# AnalogConversion_v2.net
KiCad netlist of a schematic drawn in EAGLE
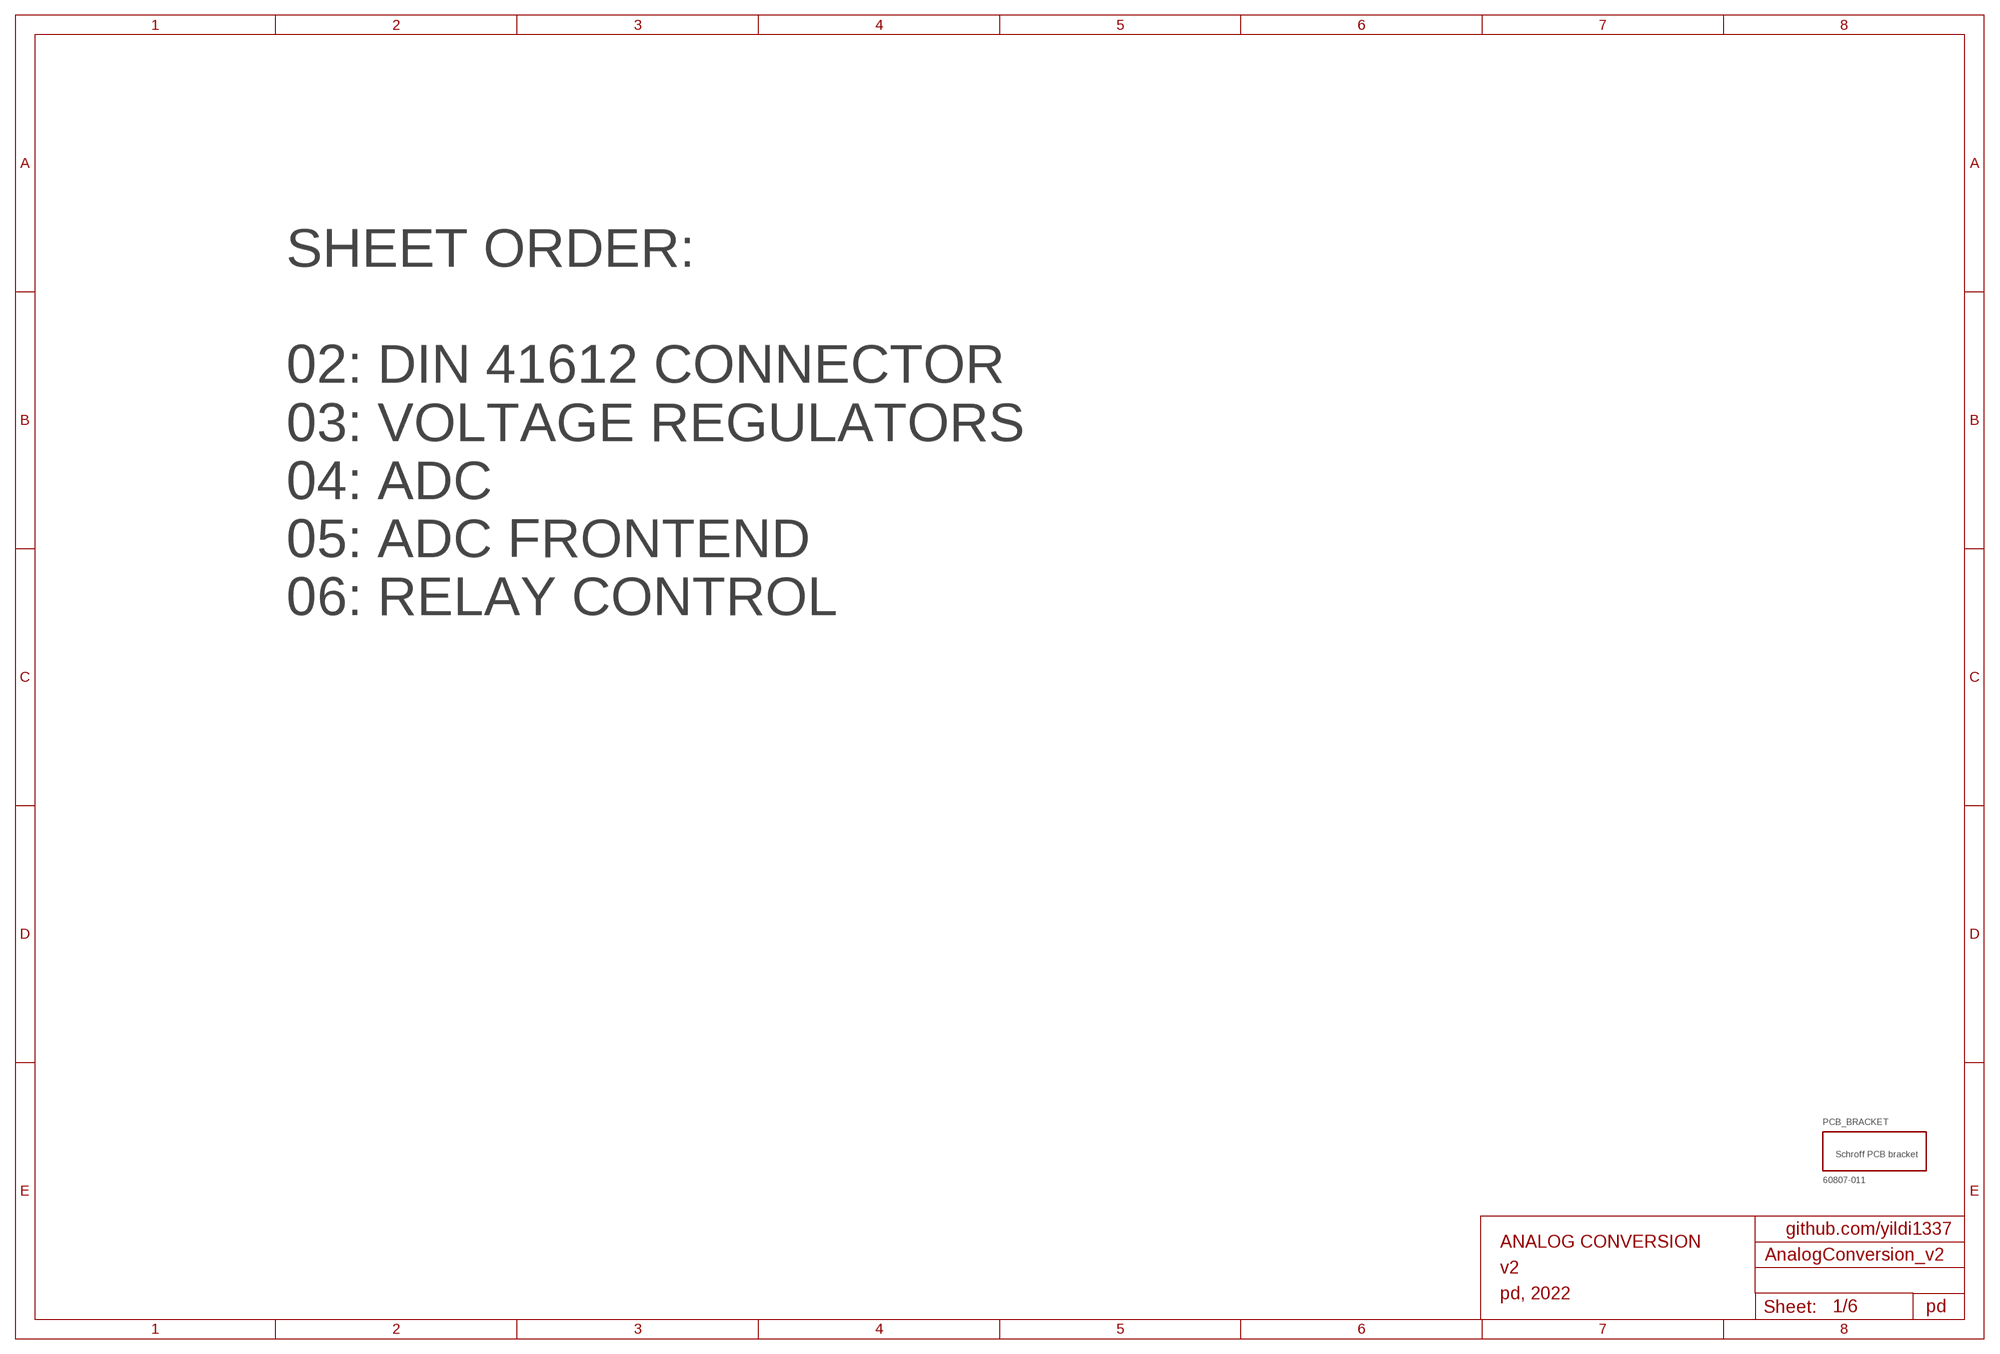
[diagram p0: schematic, sheet 1]
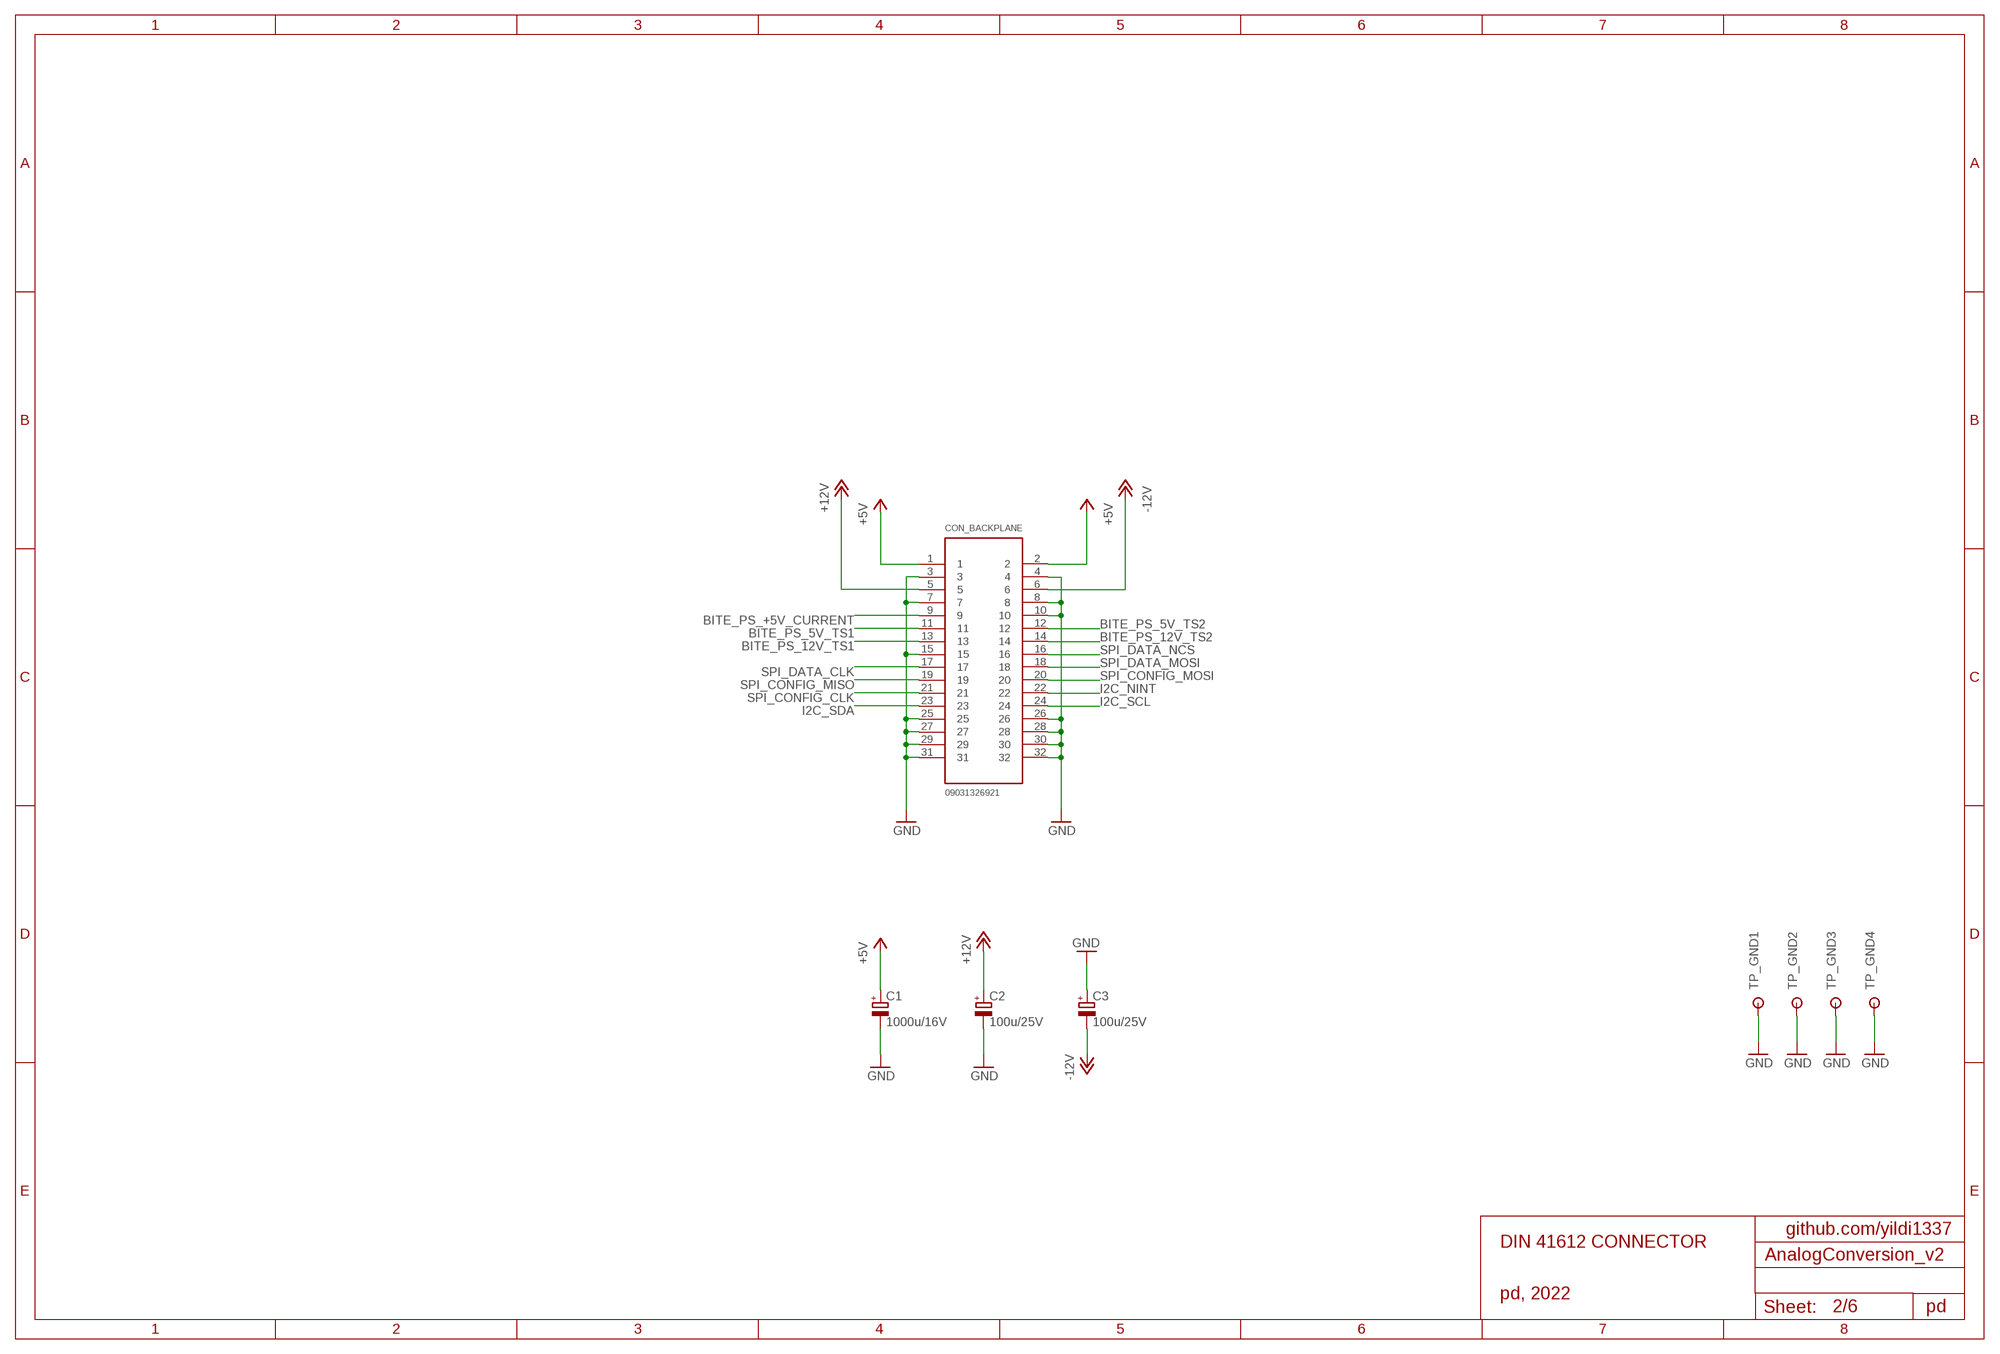
[diagram p1: schematic, sheet 2]
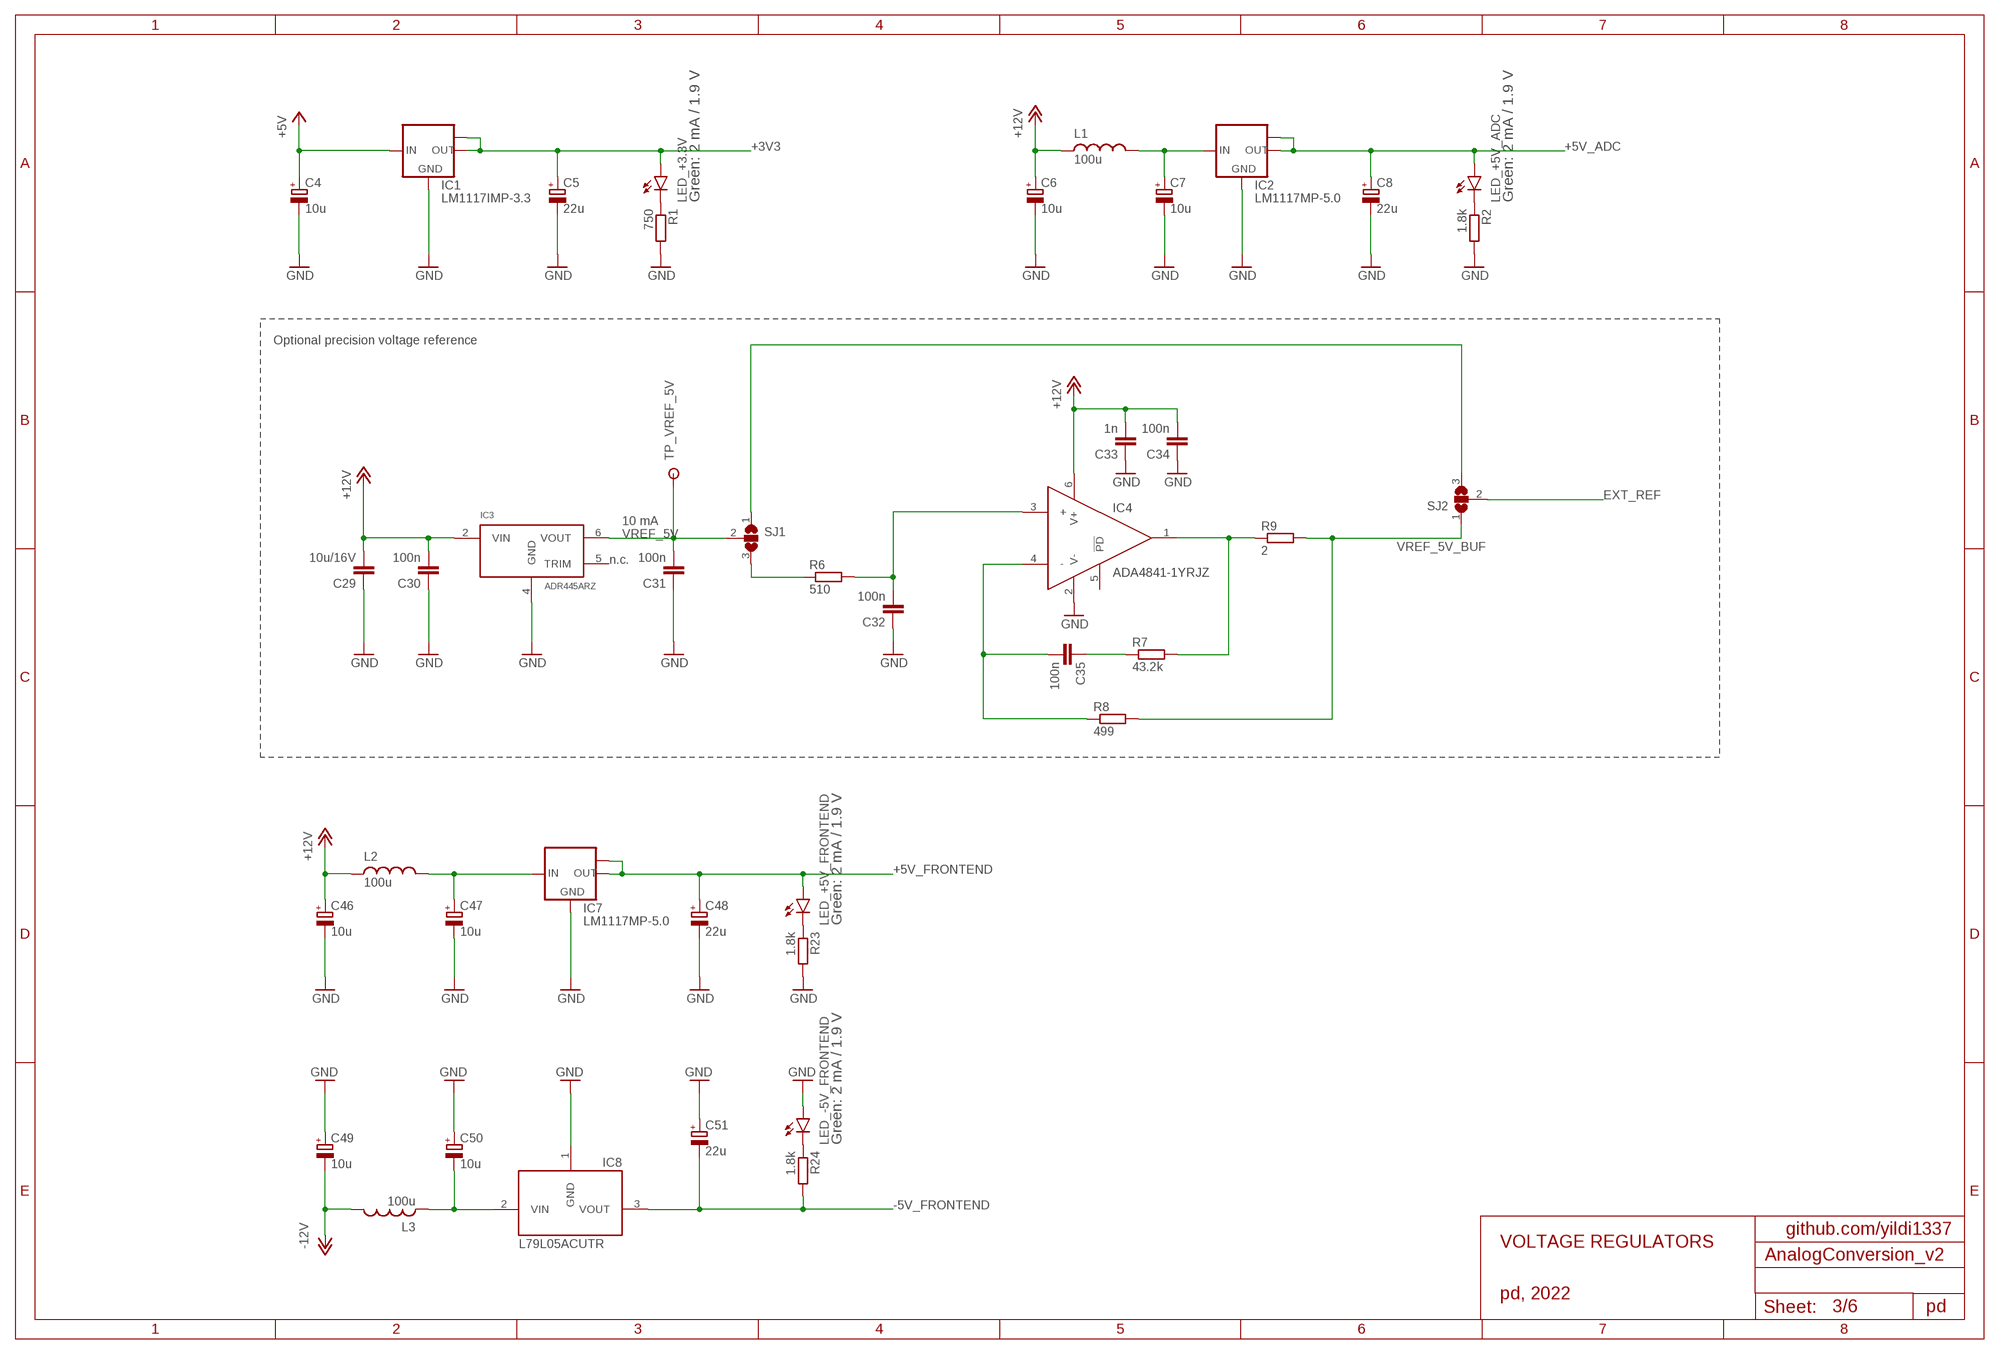
[diagram p2: schematic, sheet 3]
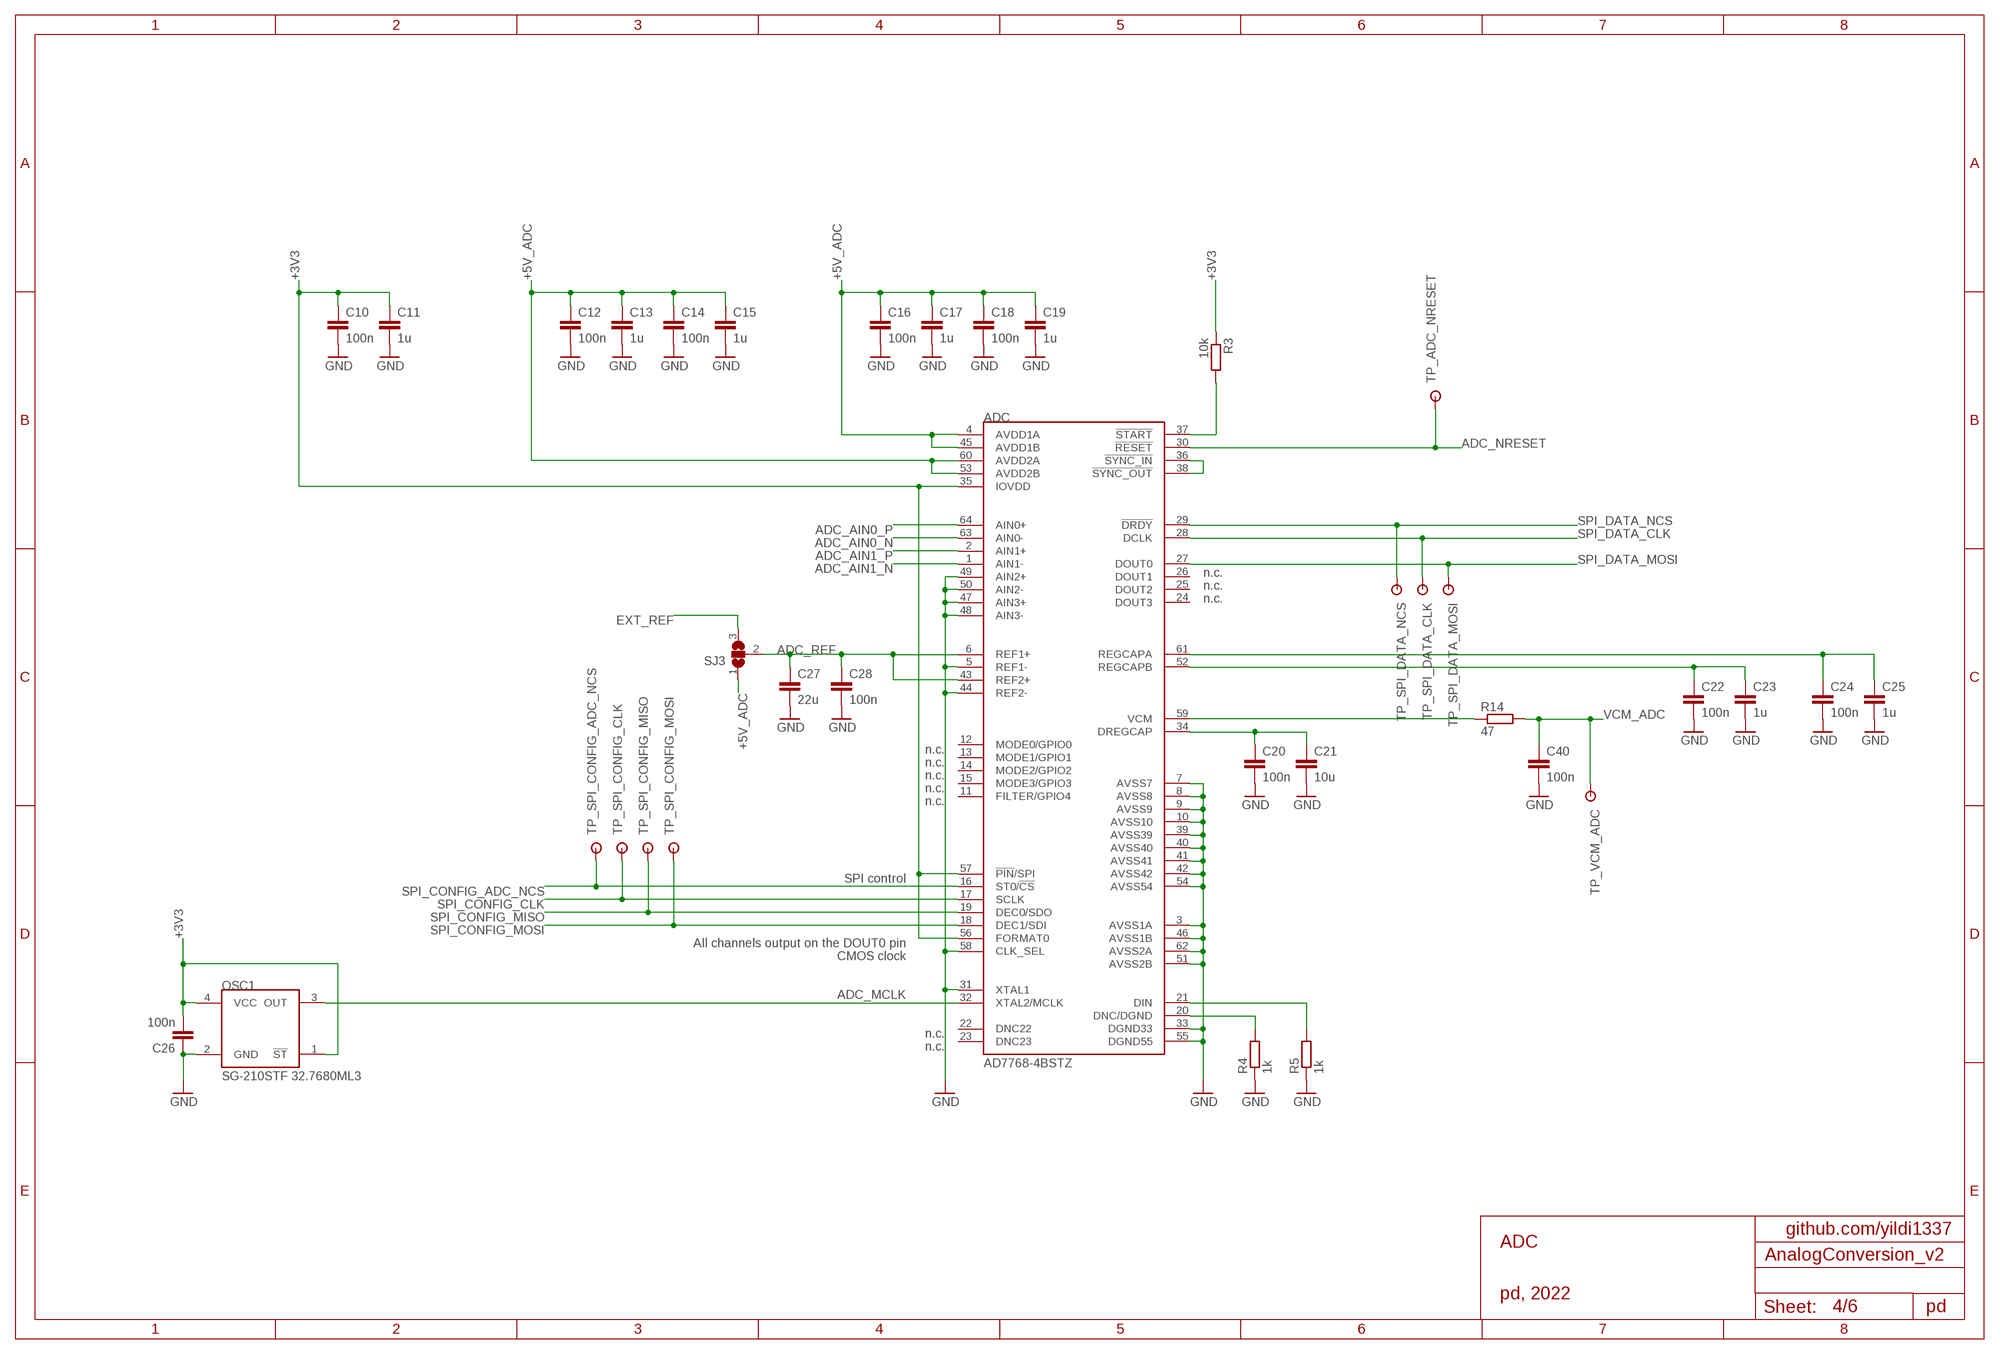
[diagram p3: schematic, sheet 4]
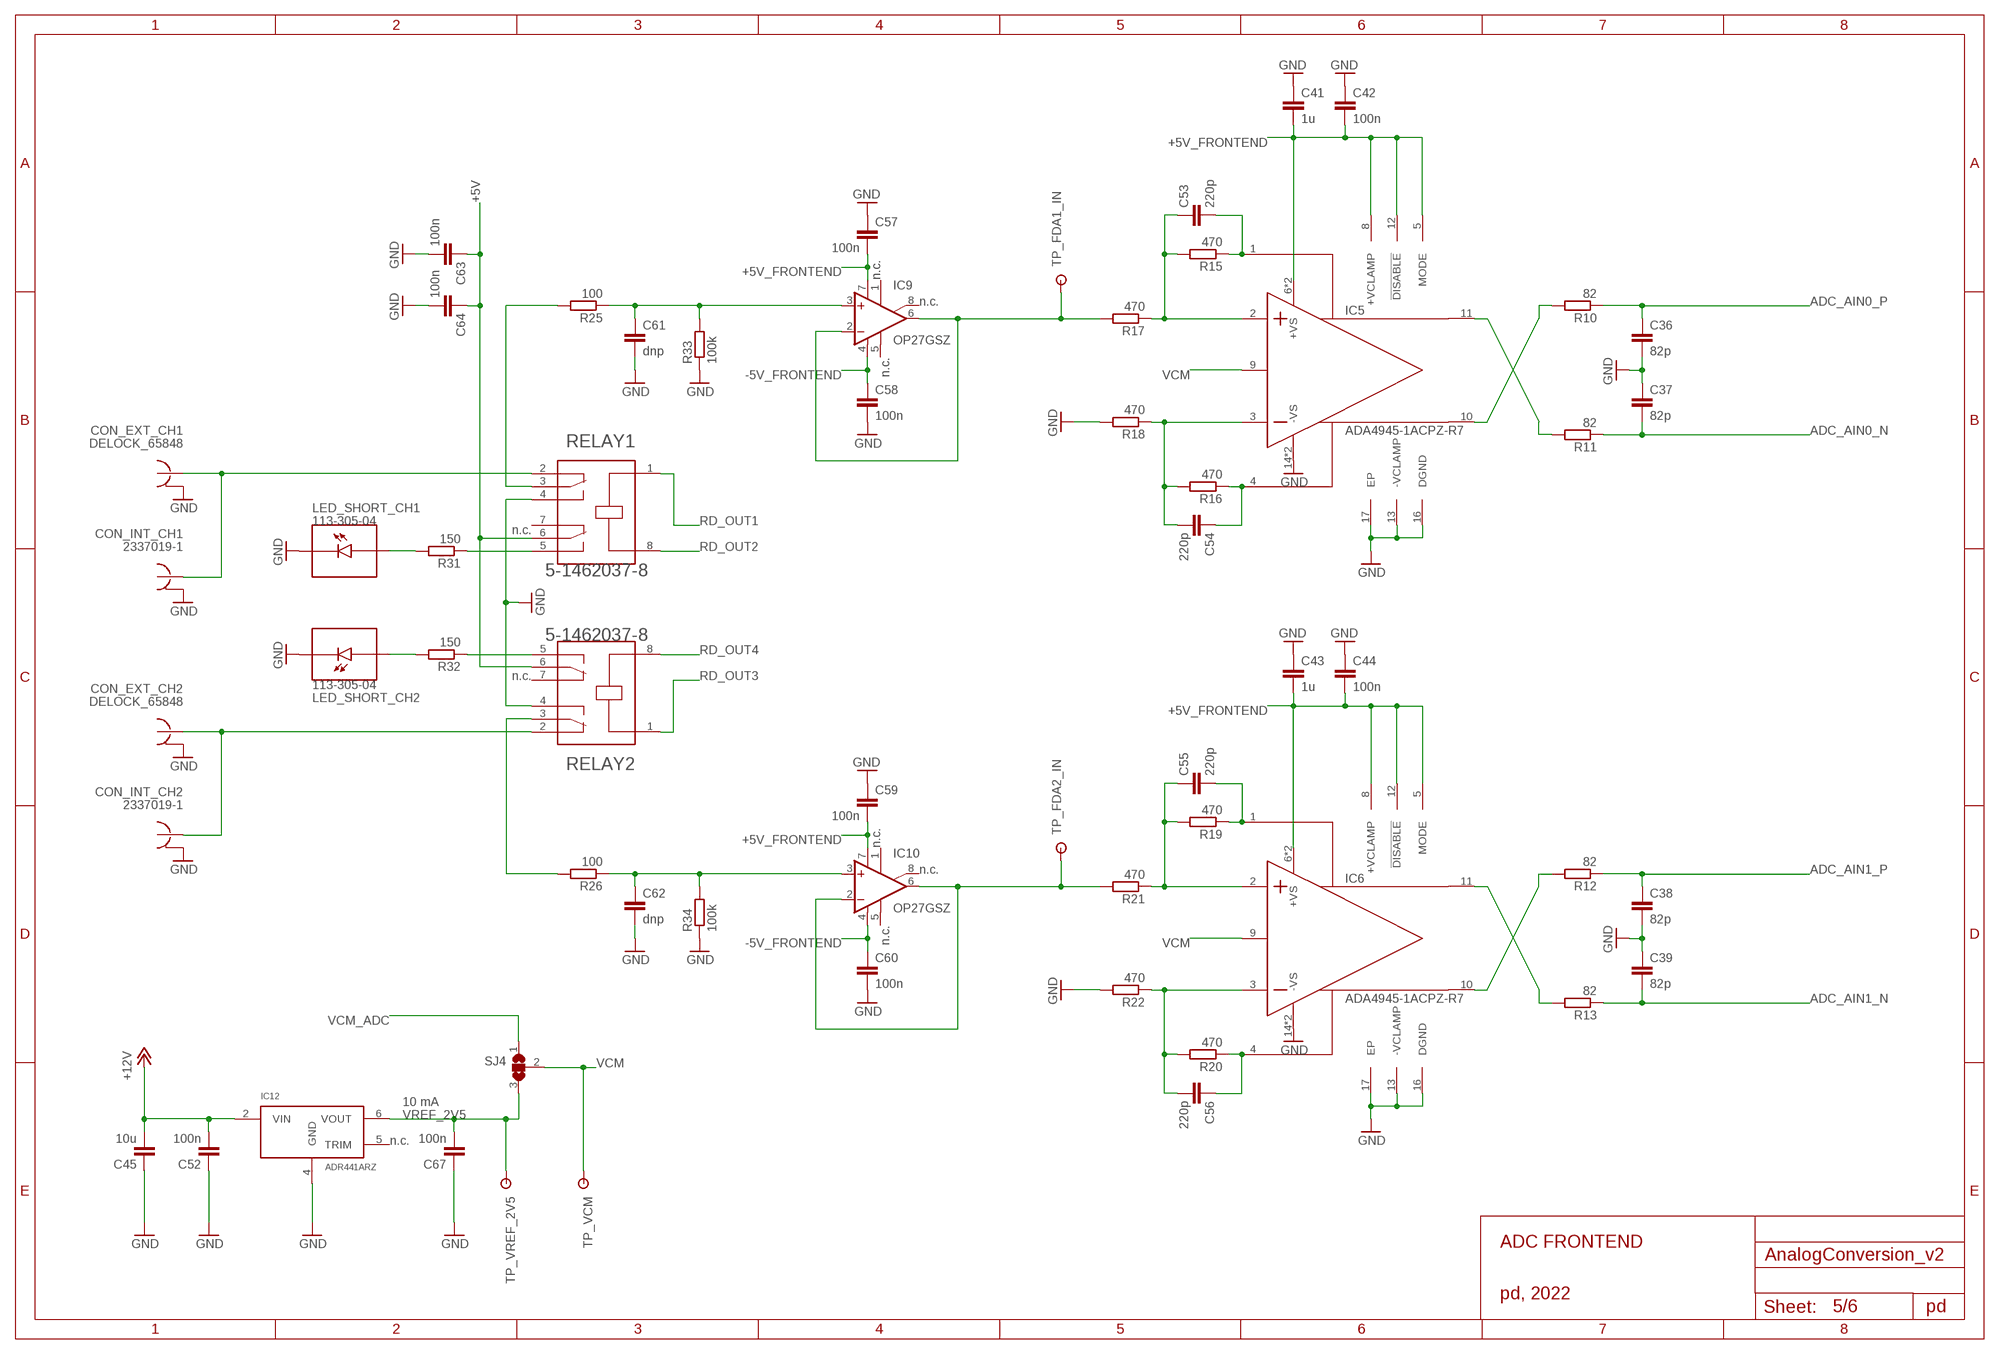
[diagram p4: schematic, sheet 5]
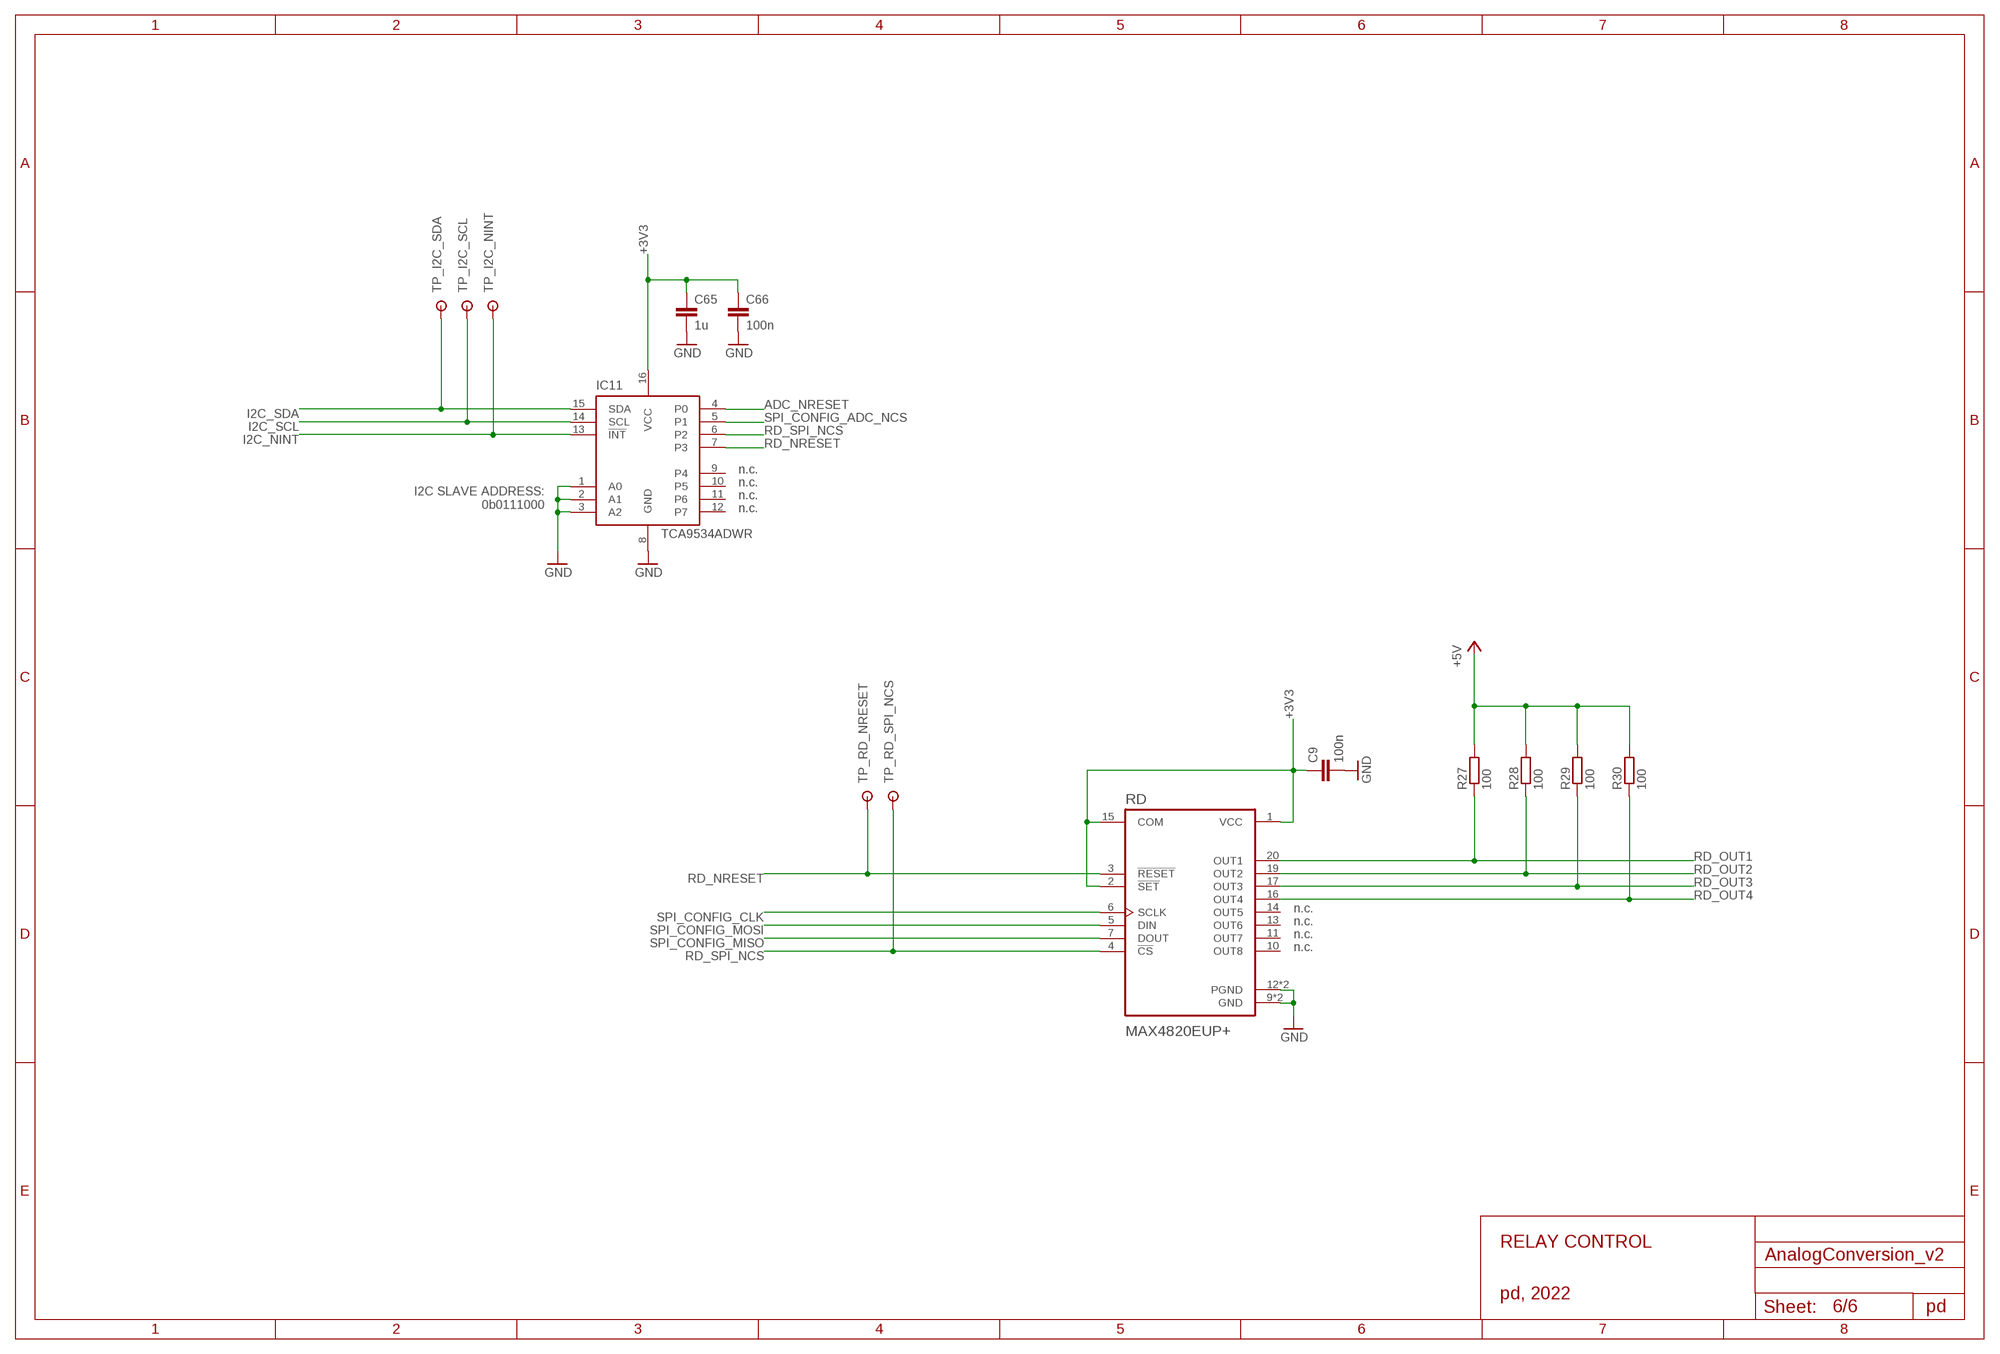
[diagram p5: schematic, sheet 6]

(export (version "E")
  (design (tool "Eeschema 10.0.6"))
  (components
    (comp (ref "ADC")
      (value "AD7768-4BSTZ")
      (footprint "eagle-import:AD7768-4BSTZ")
      (libsource (lib "eagle-import") (part "AD7768-4BSTZ"))
    )
    (comp (ref "C10")
      (value "100n")
      (footprint "eagle-import:C0603")
      (libsource (lib "eagle-import") (part "C-EUC0603"))
    )
    (comp (ref "C11")
      (value "1u")
      (footprint "eagle-import:C0603")
      (libsource (lib "eagle-import") (part "C-EUC0603"))
    )
    (comp (ref "C12")
      (value "100n")
      (footprint "eagle-import:C0603")
      (libsource (lib "eagle-import") (part "C-EUC0603"))
    )
    (comp (ref "C13")
      (value "1u")
      (footprint "eagle-import:C0603")
      (libsource (lib "eagle-import") (part "C-EUC0603"))
    )
    (comp (ref "C14")
      (value "100n")
      (footprint "eagle-import:C0603")
      (libsource (lib "eagle-import") (part "C-EUC0603"))
    )
    (comp (ref "C15")
      (value "1u")
      (footprint "eagle-import:C0603")
      (libsource (lib "eagle-import") (part "C-EUC0603"))
    )
    (comp (ref "C16")
      (value "100n")
      (footprint "eagle-import:C0603")
      (libsource (lib "eagle-import") (part "C-EUC0603"))
    )
    (comp (ref "C17")
      (value "1u")
      (footprint "eagle-import:C0603")
      (libsource (lib "eagle-import") (part "C-EUC0603"))
    )
    (comp (ref "C18")
      (value "100n")
      (footprint "eagle-import:C0603")
      (libsource (lib "eagle-import") (part "C-EUC0603"))
    )
    (comp (ref "C19")
      (value "1u")
      (footprint "eagle-import:C0603")
      (libsource (lib "eagle-import") (part "C-EUC0603"))
    )
    (comp (ref "C20")
      (value "100n")
      (footprint "eagle-import:C0603")
      (libsource (lib "eagle-import") (part "C-EUC0603"))
    )
    (comp (ref "C21")
      (value "10u")
      (footprint "eagle-import:C0603")
      (libsource (lib "eagle-import") (part "C-EUC0603"))
    )
    (comp (ref "C22")
      (value "100n")
      (footprint "eagle-import:C0603")
      (libsource (lib "eagle-import") (part "C-EUC0603"))
    )
    (comp (ref "C23")
      (value "1u")
      (footprint "eagle-import:C0603")
      (libsource (lib "eagle-import") (part "C-EUC0603"))
    )
    (comp (ref "C24")
      (value "100n")
      (footprint "eagle-import:C0603")
      (libsource (lib "eagle-import") (part "C-EUC0603"))
    )
    (comp (ref "C25")
      (value "1u")
      (footprint "eagle-import:C0603")
      (libsource (lib "eagle-import") (part "C-EUC0603"))
    )
    (comp (ref "C26")
      (value "100n")
      (footprint "eagle-import:C0603")
      (libsource (lib "eagle-import") (part "C-EUC0603"))
    )
    (comp (ref "C27")
      (value "22u")
      (footprint "eagle-import:C1206")
      (libsource (lib "eagle-import") (part "C-EUC1206"))
    )
    (comp (ref "C28")
      (value "100n")
      (footprint "eagle-import:C0603")
      (libsource (lib "eagle-import") (part "C-EUC0603"))
    )
    (comp (ref "C40")
      (value "100n")
      (footprint "eagle-import:C0603")
      (libsource (lib "eagle-import") (part "C-EUC0603"))
    )
    (comp (ref "OSC1")
      (value "SG-210STF 32.7680ML3")
      (footprint "eagle-import:SG-210STF-32.7680ML3")
      (libsource (lib "eagle-import") (part "SG-210STF-32.7680ML3"))
    )
    (comp (ref "R3")
      (value "10k")
      (footprint "eagle-import:R0603")
      (libsource (lib "eagle-import") (part "R-EU_R0603"))
    )
    (comp (ref "R4")
      (value "1k")
      (footprint "eagle-import:R0603")
      (libsource (lib "eagle-import") (part "R-EU_R0603"))
    )
    (comp (ref "R5")
      (value "1k")
      (footprint "eagle-import:R0603")
      (libsource (lib "eagle-import") (part "R-EU_R0603"))
    )
    (comp (ref "R14")
      (value "47")
      (footprint "eagle-import:R0603")
      (libsource (lib "eagle-import") (part "R-EU_R0603"))
    )
    (comp (ref "SJ3")
      (value "SJ2W")
      (footprint "eagle-import:SJ_2")
      (libsource (lib "eagle-import") (part "SJ2W"))
    )
    (comp (ref "TP_ADC_NRESET")
      (value "RSPRO-1MM-TERMINAL-POST-2622034")
      (footprint "eagle-import:RSPRO-1MM-TERMINAL-POST-2622034")
      (libsource (lib "eagle-import") (part "RSPRO-1MM-TERMINAL-POST-2622034"))
    )
    (comp (ref "TP_SPI_CONFIG_ADC_NCS")
      (value "RSPRO-1MM-TERMINAL-POST-2622034")
      (footprint "eagle-import:RSPRO-1MM-TERMINAL-POST-2622034")
      (libsource (lib "eagle-import") (part "RSPRO-1MM-TERMINAL-POST-2622034"))
    )
    (comp (ref "TP_SPI_CONFIG_CLK")
      (value "RSPRO-1MM-TERMINAL-POST-2622034")
      (footprint "eagle-import:RSPRO-1MM-TERMINAL-POST-2622034")
      (libsource (lib "eagle-import") (part "RSPRO-1MM-TERMINAL-POST-2622034"))
    )
    (comp (ref "TP_SPI_CONFIG_MISO")
      (value "RSPRO-1MM-TERMINAL-POST-2622034")
      (footprint "eagle-import:RSPRO-1MM-TERMINAL-POST-2622034")
      (libsource (lib "eagle-import") (part "RSPRO-1MM-TERMINAL-POST-2622034"))
    )
    (comp (ref "TP_SPI_CONFIG_MOSI")
      (value "RSPRO-1MM-TERMINAL-POST-2622034")
      (footprint "eagle-import:RSPRO-1MM-TERMINAL-POST-2622034")
      (libsource (lib "eagle-import") (part "RSPRO-1MM-TERMINAL-POST-2622034"))
    )
    (comp (ref "TP_SPI_DATA_CLK")
      (value "RSPRO-1MM-TERMINAL-POST-2622034")
      (footprint "eagle-import:RSPRO-1MM-TERMINAL-POST-2622034")
      (libsource (lib "eagle-import") (part "RSPRO-1MM-TERMINAL-POST-2622034"))
    )
    (comp (ref "TP_SPI_DATA_MOSI")
      (value "RSPRO-1MM-TERMINAL-POST-2622034")
      (footprint "eagle-import:RSPRO-1MM-TERMINAL-POST-2622034")
      (libsource (lib "eagle-import") (part "RSPRO-1MM-TERMINAL-POST-2622034"))
    )
    (comp (ref "TP_SPI_DATA_NCS")
      (value "RSPRO-1MM-TERMINAL-POST-2622034")
      (footprint "eagle-import:RSPRO-1MM-TERMINAL-POST-2622034")
      (libsource (lib "eagle-import") (part "RSPRO-1MM-TERMINAL-POST-2622034"))
    )
    (comp (ref "TP_VCM_ADC")
      (value "RSPRO-1MM-TERMINAL-POST-2622034")
      (footprint "eagle-import:RSPRO-1MM-TERMINAL-POST-2622034")
      (libsource (lib "eagle-import") (part "RSPRO-1MM-TERMINAL-POST-2622034"))
    )
    (comp (ref "PCB_BRACKET")
      (value "60807-011")
      (footprint "eagle-import:60807-011")
      (libsource (lib "eagle-import") (part "60807-011"))
    )
    (comp (ref "C9")
      (value "100n")
      (footprint "eagle-import:C0603")
      (libsource (lib "eagle-import") (part "C-EUC0603"))
    )
    (comp (ref "C65")
      (value "1u")
      (footprint "eagle-import:C0603")
      (libsource (lib "eagle-import") (part "C-EUC0603"))
    )
    (comp (ref "C66")
      (value "100n")
      (footprint "eagle-import:C0603")
      (libsource (lib "eagle-import") (part "C-EUC0603"))
    )
    (comp (ref "IC11")
      (value "TCA9534ADWR")
      (footprint "eagle-import:TCA9534ADWR")
      (libsource (lib "eagle-import") (part "TCA9534ADWR"))
    )
    (comp (ref "R27")
      (value "100")
      (footprint "eagle-import:R0603")
      (libsource (lib "eagle-import") (part "R-EU_R0603"))
    )
    (comp (ref "R28")
      (value "100")
      (footprint "eagle-import:R0603")
      (libsource (lib "eagle-import") (part "R-EU_R0603"))
    )
    (comp (ref "R29")
      (value "100")
      (footprint "eagle-import:R0603")
      (libsource (lib "eagle-import") (part "R-EU_R0603"))
    )
    (comp (ref "R30")
      (value "100")
      (footprint "eagle-import:R0603")
      (libsource (lib "eagle-import") (part "R-EU_R0603"))
    )
    (comp (ref "RD")
      (value "MAX4820EUP+")
      (footprint "eagle-import:MAX4820EUP+")
      (libsource (lib "eagle-import") (part "MAX4820EUP+"))
    )
    (comp (ref "TP_I2C_NINT")
      (value "RSPRO-1MM-TERMINAL-POST-2622034")
      (footprint "eagle-import:RSPRO-1MM-TERMINAL-POST-2622034")
      (libsource (lib "eagle-import") (part "RSPRO-1MM-TERMINAL-POST-2622034"))
    )
    (comp (ref "TP_I2C_SCL")
      (value "RSPRO-1MM-TERMINAL-POST-2622034")
      (footprint "eagle-import:RSPRO-1MM-TERMINAL-POST-2622034")
      (libsource (lib "eagle-import") (part "RSPRO-1MM-TERMINAL-POST-2622034"))
    )
    (comp (ref "TP_I2C_SDA")
      (value "RSPRO-1MM-TERMINAL-POST-2622034")
      (footprint "eagle-import:RSPRO-1MM-TERMINAL-POST-2622034")
      (libsource (lib "eagle-import") (part "RSPRO-1MM-TERMINAL-POST-2622034"))
    )
    (comp (ref "TP_RD_NRESET")
      (value "RSPRO-1MM-TERMINAL-POST-2622034")
      (footprint "eagle-import:RSPRO-1MM-TERMINAL-POST-2622034")
      (libsource (lib "eagle-import") (part "RSPRO-1MM-TERMINAL-POST-2622034"))
    )
    (comp (ref "TP_RD_SPI_NCS")
      (value "RSPRO-1MM-TERMINAL-POST-2622034")
      (footprint "eagle-import:RSPRO-1MM-TERMINAL-POST-2622034")
      (libsource (lib "eagle-import") (part "RSPRO-1MM-TERMINAL-POST-2622034"))
    )
    (comp (ref "C4")
      (value "10u")
      (footprint "eagle-import:CT3216")
      (libsource (lib "eagle-import") (part "CPOL-EUCT3216"))
    )
    (comp (ref "C5")
      (value "22u")
      (footprint "eagle-import:CT6032")
      (libsource (lib "eagle-import") (part "CPOL-EUCT6032"))
    )
    (comp (ref "C6")
      (value "10u")
      (footprint "eagle-import:CT3216")
      (libsource (lib "eagle-import") (part "CPOL-EUCT3216"))
    )
    (comp (ref "C7")
      (value "10u")
      (footprint "eagle-import:CT3216")
      (libsource (lib "eagle-import") (part "CPOL-EUCT3216"))
    )
    (comp (ref "C8")
      (value "22u")
      (footprint "eagle-import:CT6032")
      (libsource (lib "eagle-import") (part "CPOL-EUCT6032"))
    )
    (comp (ref "C29")
      (value "10u/16V")
      (footprint "eagle-import:C0805")
      (libsource (lib "eagle-import") (part "C-EUC0805"))
    )
    (comp (ref "C30")
      (value "100n")
      (footprint "eagle-import:C0603")
      (libsource (lib "eagle-import") (part "C-EUC0603"))
    )
    (comp (ref "C31")
      (value "100n")
      (footprint "eagle-import:C0603")
      (libsource (lib "eagle-import") (part "C-EUC0603"))
    )
    (comp (ref "C32")
      (value "100n")
      (footprint "eagle-import:C0603")
      (libsource (lib "eagle-import") (part "C-EUC0603"))
    )
    (comp (ref "C33")
      (value "1n")
      (footprint "eagle-import:C0603")
      (libsource (lib "eagle-import") (part "C-EUC0603"))
    )
    (comp (ref "C34")
      (value "100n")
      (footprint "eagle-import:C0603")
      (libsource (lib "eagle-import") (part "C-EUC0603"))
    )
    (comp (ref "C35")
      (value "100n")
      (footprint "eagle-import:C0603")
      (libsource (lib "eagle-import") (part "C-EUC0603"))
    )
    (comp (ref "C46")
      (value "10u")
      (footprint "eagle-import:CT3216")
      (libsource (lib "eagle-import") (part "CPOL-EUCT3216"))
    )
    (comp (ref "C47")
      (value "10u")
      (footprint "eagle-import:CT3216")
      (libsource (lib "eagle-import") (part "CPOL-EUCT3216"))
    )
    (comp (ref "C48")
      (value "22u")
      (footprint "eagle-import:CT6032")
      (libsource (lib "eagle-import") (part "CPOL-EUCT6032"))
    )
    (comp (ref "C49")
      (value "10u")
      (footprint "eagle-import:CT3216")
      (libsource (lib "eagle-import") (part "CPOL-EUCT3216"))
    )
    (comp (ref "C50")
      (value "10u")
      (footprint "eagle-import:CT3216")
      (libsource (lib "eagle-import") (part "CPOL-EUCT3216"))
    )
    (comp (ref "C51")
      (value "22u")
      (footprint "eagle-import:CT6032")
      (libsource (lib "eagle-import") (part "CPOL-EUCT6032"))
    )
    (comp (ref "IC1")
      (value "LM1117IMP-3.3")
      (footprint "eagle-import:SOT223")
      (libsource (lib "eagle-import") (part "LM1117IMPX-3.3"))
    )
    (comp (ref "IC2")
      (value "LM1117MP-5.0")
      (footprint "eagle-import:SOT223")
      (libsource (lib "eagle-import") (part "LM1117MPX-5.0"))
    )
    (comp (ref "IC3")
      (value "ADR445ARZ")
      (footprint "eagle-import:ADR445ARZ")
      (libsource (lib "eagle-import") (part "ADR445ARZ"))
    )
    (comp (ref "IC4")
      (value "ADA4841-1YRJZ")
      (footprint "eagle-import:ADA4841-1YRJZ")
      (libsource (lib "eagle-import") (part "ADA4841-1YRJZ"))
    )
    (comp (ref "IC7")
      (value "LM1117MP-5.0")
      (footprint "eagle-import:SOT223")
      (libsource (lib "eagle-import") (part "LM1117MPX-5.0"))
    )
    (comp (ref "IC8")
      (value "L79L05ACUTR")
      (footprint "eagle-import:L79L05ACUTR")
      (libsource (lib "eagle-import") (part "L79L05ACUTR"))
    )
    (comp (ref "L1")
      (value "100u")
      (footprint "eagle-import:VLS6045AF-101M")
      (libsource (lib "eagle-import") (part "VLS6045AF-101M"))
    )
    (comp (ref "L2")
      (value "100u")
      (footprint "eagle-import:VLS6045AF-101M")
      (libsource (lib "eagle-import") (part "VLS6045AF-101M"))
    )
    (comp (ref "L3")
      (value "100u")
      (footprint "eagle-import:VLS6045AF-101M")
      (libsource (lib "eagle-import") (part "VLS6045AF-101M"))
    )
    (comp (ref "LED_+3.3V")
      (value "LEDCHIP-LED0603")
      (footprint "eagle-import:CHIP-LED0603")
      (libsource (lib "eagle-import") (part "LEDCHIP-LED0603"))
    )
    (comp (ref "LED_+5V_ADC")
      (value "LEDCHIP-LED0603")
      (footprint "eagle-import:CHIP-LED0603")
      (libsource (lib "eagle-import") (part "LEDCHIP-LED0603"))
    )
    (comp (ref "LED_+5V_FRONTEND")
      (value "LEDCHIP-LED0603")
      (footprint "eagle-import:CHIP-LED0603")
      (libsource (lib "eagle-import") (part "LEDCHIP-LED0603"))
    )
    (comp (ref "LED_-5V_FRONTEND")
      (value "LEDCHIP-LED0603")
      (footprint "eagle-import:CHIP-LED0603")
      (libsource (lib "eagle-import") (part "LEDCHIP-LED0603"))
    )
    (comp (ref "R1")
      (value "750")
      (footprint "eagle-import:R0603")
      (libsource (lib "eagle-import") (part "R-EU_R0603"))
    )
    (comp (ref "R2")
      (value "1.8k")
      (footprint "eagle-import:R0603")
      (libsource (lib "eagle-import") (part "R-EU_R0603"))
    )
    (comp (ref "R6")
      (value "510")
      (footprint "eagle-import:R0603")
      (libsource (lib "eagle-import") (part "R-EU_R0603"))
    )
    (comp (ref "R7")
      (value "43.2k")
      (footprint "eagle-import:R0603")
      (libsource (lib "eagle-import") (part "R-EU_R0603"))
    )
    (comp (ref "R8")
      (value "499")
      (footprint "eagle-import:R0603")
      (libsource (lib "eagle-import") (part "R-EU_R0603"))
    )
    (comp (ref "R9")
      (value "2")
      (footprint "eagle-import:R0603")
      (libsource (lib "eagle-import") (part "R-EU_R0603"))
    )
    (comp (ref "R23")
      (value "1.8k")
      (footprint "eagle-import:R0603")
      (libsource (lib "eagle-import") (part "R-EU_R0603"))
    )
    (comp (ref "R24")
      (value "1.8k")
      (footprint "eagle-import:R0603")
      (libsource (lib "eagle-import") (part "R-EU_R0603"))
    )
    (comp (ref "SJ1")
      (value "SJ2W")
      (footprint "eagle-import:SJ_2")
      (libsource (lib "eagle-import") (part "SJ2W"))
    )
    (comp (ref "SJ2")
      (value "SJ2W")
      (footprint "eagle-import:SJ_2")
      (libsource (lib "eagle-import") (part "SJ2W"))
    )
    (comp (ref "TP_VREF_5V")
      (value "RSPRO-1MM-TERMINAL-POST-2622034")
      (footprint "eagle-import:RSPRO-1MM-TERMINAL-POST-2622034")
      (libsource (lib "eagle-import") (part "RSPRO-1MM-TERMINAL-POST-2622034"))
    )
    (comp (ref "C1")
      (value "1000u/16V")
      (footprint "eagle-import:153CLV-1010")
      (libsource (lib "eagle-import") (part "rcl_18640681_CPOL-EU153CLV-1010"))
    )
    (comp (ref "C2")
      (value "100u/25V")
      (footprint "eagle-import:153CLV-0810")
      (libsource (lib "eagle-import") (part "rcl_18640681_CPOL-EU153CLV-0810"))
    )
    (comp (ref "C3")
      (value "100u/25V")
      (footprint "eagle-import:153CLV-0810")
      (libsource (lib "eagle-import") (part "rcl_18640681_CPOL-EU153CLV-0810"))
    )
    (comp (ref "CON_BACKPLANE")
      (value "09031326921")
      (footprint "eagle-import:09031326921")
      (libsource (lib "eagle-import") (part "09031326921"))
    )
    (comp (ref "TP_GND1")
      (value "RSPRO-1MM-TERMINAL-POST-2622034")
      (footprint "eagle-import:RSPRO-1MM-TERMINAL-POST-2622034")
      (libsource (lib "eagle-import") (part "RSPRO-1MM-TERMINAL-POST-2622034"))
    )
    (comp (ref "TP_GND2")
      (value "RSPRO-1MM-TERMINAL-POST-2622034")
      (footprint "eagle-import:RSPRO-1MM-TERMINAL-POST-2622034")
      (libsource (lib "eagle-import") (part "RSPRO-1MM-TERMINAL-POST-2622034"))
    )
    (comp (ref "TP_GND3")
      (value "RSPRO-1MM-TERMINAL-POST-2622034")
      (footprint "eagle-import:RSPRO-1MM-TERMINAL-POST-2622034")
      (libsource (lib "eagle-import") (part "RSPRO-1MM-TERMINAL-POST-2622034"))
    )
    (comp (ref "TP_GND4")
      (value "RSPRO-1MM-TERMINAL-POST-2622034")
      (footprint "eagle-import:RSPRO-1MM-TERMINAL-POST-2622034")
      (libsource (lib "eagle-import") (part "RSPRO-1MM-TERMINAL-POST-2622034"))
    )
    (comp (ref "C36")
      (value "82p")
      (footprint "eagle-import:C0603")
      (libsource (lib "eagle-import") (part "C-EUC0603"))
    )
    (comp (ref "C37")
      (value "82p")
      (footprint "eagle-import:C0603")
      (libsource (lib "eagle-import") (part "C-EUC0603"))
    )
    (comp (ref "C38")
      (value "82p")
      (footprint "eagle-import:C0603")
      (libsource (lib "eagle-import") (part "C-EUC0603"))
    )
    (comp (ref "C39")
      (value "82p")
      (footprint "eagle-import:C0603")
      (libsource (lib "eagle-import") (part "C-EUC0603"))
    )
    (comp (ref "C41")
      (value "1u")
      (footprint "eagle-import:C0603")
      (libsource (lib "eagle-import") (part "C-EUC0603"))
    )
    (comp (ref "C42")
      (value "100n")
      (footprint "eagle-import:C0603")
      (libsource (lib "eagle-import") (part "C-EUC0603"))
    )
    (comp (ref "C43")
      (value "1u")
      (footprint "eagle-import:C0603")
      (libsource (lib "eagle-import") (part "C-EUC0603"))
    )
    (comp (ref "C44")
      (value "100n")
      (footprint "eagle-import:C0603")
      (libsource (lib "eagle-import") (part "C-EUC0603"))
    )
    (comp (ref "C45")
      (value "10u")
      (footprint "eagle-import:C0805")
      (libsource (lib "eagle-import") (part "C-EUC0805"))
    )
    (comp (ref "C52")
      (value "100n")
      (footprint "eagle-import:C0603")
      (libsource (lib "eagle-import") (part "C-EUC0603"))
    )
    (comp (ref "C53")
      (value "220p")
      (footprint "eagle-import:C0603")
      (libsource (lib "eagle-import") (part "C-EUC0603"))
    )
    (comp (ref "C54")
      (value "220p")
      (footprint "eagle-import:C0603")
      (libsource (lib "eagle-import") (part "C-EUC0603"))
    )
    (comp (ref "C55")
      (value "220p")
      (footprint "eagle-import:C0603")
      (libsource (lib "eagle-import") (part "C-EUC0603"))
    )
    (comp (ref "C56")
      (value "220p")
      (footprint "eagle-import:C0603")
      (libsource (lib "eagle-import") (part "C-EUC0603"))
    )
    (comp (ref "C57")
      (value "100n")
      (footprint "eagle-import:C0603")
      (libsource (lib "eagle-import") (part "C-EUC0603"))
    )
    (comp (ref "C58")
      (value "100n")
      (footprint "eagle-import:C0603")
      (libsource (lib "eagle-import") (part "C-EUC0603"))
    )
    (comp (ref "C59")
      (value "100n")
      (footprint "eagle-import:C0603")
      (libsource (lib "eagle-import") (part "C-EUC0603"))
    )
    (comp (ref "C60")
      (value "100n")
      (footprint "eagle-import:C0603")
      (libsource (lib "eagle-import") (part "C-EUC0603"))
    )
    (comp (ref "C61")
      (value "dnp")
      (footprint "eagle-import:C0603")
      (libsource (lib "eagle-import") (part "C-EUC0603"))
    )
    (comp (ref "C62")
      (value "dnp")
      (footprint "eagle-import:C0603")
      (libsource (lib "eagle-import") (part "C-EUC0603"))
    )
    (comp (ref "C63")
      (value "100n")
      (footprint "eagle-import:C0603")
      (libsource (lib "eagle-import") (part "C-EUC0603"))
    )
    (comp (ref "C64")
      (value "100n")
      (footprint "eagle-import:C0603")
      (libsource (lib "eagle-import") (part "C-EUC0603"))
    )
    (comp (ref "C67")
      (value "100n")
      (footprint "eagle-import:C0603")
      (libsource (lib "eagle-import") (part "C-EUC0603"))
    )
    (comp (ref "CON_EXT_CH1")
      (value "DELOCK_65848")
      (footprint "eagle-import:DELOCK_65848")
      (libsource (lib "eagle-import") (part "DELOCK_65848"))
    )
    (comp (ref "CON_EXT_CH2")
      (value "DELOCK_65848")
      (footprint "eagle-import:DELOCK_65848")
      (libsource (lib "eagle-import") (part "DELOCK_65848"))
    )
    (comp (ref "CON_INT_CH1")
      (value "2337019-1")
      (footprint "eagle-import:2337019-1")
      (libsource (lib "eagle-import") (part "2337019-1"))
    )
    (comp (ref "CON_INT_CH2")
      (value "2337019-1")
      (footprint "eagle-import:2337019-1")
      (libsource (lib "eagle-import") (part "2337019-1"))
    )
    (comp (ref "IC5")
      (value "ADA4945-1ACPZ-R7")
      (footprint "eagle-import:ADA4945-1ACPZ-R7")
      (libsource (lib "eagle-import") (part "ADA4945-1ACPZ-R7"))
    )
    (comp (ref "IC6")
      (value "ADA4945-1ACPZ-R7")
      (footprint "eagle-import:ADA4945-1ACPZ-R7")
      (libsource (lib "eagle-import") (part "ADA4945-1ACPZ-R7"))
    )
    (comp (ref "IC9")
      (value "OP27GSZ")
      (footprint "eagle-import:SO08")
      (libsource (lib "eagle-import") (part "OP27D"))
    )
    (comp (ref "IC10")
      (value "OP27GSZ")
      (footprint "eagle-import:SO08")
      (libsource (lib "eagle-import") (part "OP27D"))
    )
    (comp (ref "IC12")
      (value "ADR441ARZ")
      (footprint "eagle-import:ADR441ARZ")
      (libsource (lib "eagle-import") (part "ADR441ARZ"))
    )
    (comp (ref "LED_SHORT_CH1")
      (value "113-305-04")
      (footprint "eagle-import:113-305-04")
      (libsource (lib "eagle-import") (part "113-305-04"))
    )
    (comp (ref "LED_SHORT_CH2")
      (value "113-305-04")
      (footprint "eagle-import:113-305-04")
      (libsource (lib "eagle-import") (part "113-305-04"))
    )
    (comp (ref "R10")
      (value "82")
      (footprint "eagle-import:R0603")
      (libsource (lib "eagle-import") (part "R-EU_R0603"))
    )
    (comp (ref "R11")
      (value "82")
      (footprint "eagle-import:R0603")
      (libsource (lib "eagle-import") (part "R-EU_R0603"))
    )
    (comp (ref "R12")
      (value "82")
      (footprint "eagle-import:R0603")
      (libsource (lib "eagle-import") (part "R-EU_R0603"))
    )
    (comp (ref "R13")
      (value "82")
      (footprint "eagle-import:R0603")
      (libsource (lib "eagle-import") (part "R-EU_R0603"))
    )
    (comp (ref "R15")
      (value "470")
      (footprint "eagle-import:R0603")
      (libsource (lib "eagle-import") (part "R-EU_R0603"))
    )
    (comp (ref "R16")
      (value "470")
      (footprint "eagle-import:R0603")
      (libsource (lib "eagle-import") (part "R-EU_R0603"))
    )
    (comp (ref "R17")
      (value "470")
      (footprint "eagle-import:R0603")
      (libsource (lib "eagle-import") (part "R-EU_R0603"))
    )
    (comp (ref "R18")
      (value "470")
      (footprint "eagle-import:R0603")
      (libsource (lib "eagle-import") (part "R-EU_R0603"))
    )
    (comp (ref "R19")
      (value "470")
      (footprint "eagle-import:R0603")
      (libsource (lib "eagle-import") (part "R-EU_R0603"))
    )
    (comp (ref "R20")
      (value "470")
      (footprint "eagle-import:R0603")
      (libsource (lib "eagle-import") (part "R-EU_R0603"))
    )
    (comp (ref "R21")
      (value "470")
      (footprint "eagle-import:R0603")
      (libsource (lib "eagle-import") (part "R-EU_R0603"))
    )
    (comp (ref "R22")
      (value "470")
      (footprint "eagle-import:R0603")
      (libsource (lib "eagle-import") (part "R-EU_R0603"))
    )
    (comp (ref "R25")
      (value "100")
      (footprint "eagle-import:R0603")
      (libsource (lib "eagle-import") (part "R-EU_R0603"))
    )
    (comp (ref "R26")
      (value "100")
      (footprint "eagle-import:R0603")
      (libsource (lib "eagle-import") (part "R-EU_R0603"))
    )
    (comp (ref "R31")
      (value "150")
      (footprint "eagle-import:R0603")
      (libsource (lib "eagle-import") (part "R-EU_R0603"))
    )
    (comp (ref "R32")
      (value "150")
      (footprint "eagle-import:R0603")
      (libsource (lib "eagle-import") (part "R-EU_R0603"))
    )
    (comp (ref "R33")
      (value "100k")
      (footprint "eagle-import:R0603")
      (libsource (lib "eagle-import") (part "R-EU_R0603"))
    )
    (comp (ref "R34")
      (value "100k")
      (footprint "eagle-import:R0603")
      (libsource (lib "eagle-import") (part "R-EU_R0603"))
    )
    (comp (ref "RELAY1")
      (value "5-1462037-8")
      (footprint "eagle-import:5-1462037-8")
      (libsource (lib "eagle-import") (part "5-1462037-8"))
    )
    (comp (ref "RELAY2")
      (value "5-1462037-8")
      (footprint "eagle-import:5-1462037-8")
      (libsource (lib "eagle-import") (part "5-1462037-8"))
    )
    (comp (ref "SJ4")
      (value "SJ2W")
      (footprint "eagle-import:SJ_2")
      (libsource (lib "eagle-import") (part "SJ2W"))
    )
    (comp (ref "TP_FDA1_IN")
      (value "RSPRO-1MM-TERMINAL-POST-2622034")
      (footprint "eagle-import:RSPRO-1MM-TERMINAL-POST-2622034")
      (libsource (lib "eagle-import") (part "RSPRO-1MM-TERMINAL-POST-2622034"))
    )
    (comp (ref "TP_FDA2_IN")
      (value "RSPRO-1MM-TERMINAL-POST-2622034")
      (footprint "eagle-import:RSPRO-1MM-TERMINAL-POST-2622034")
      (libsource (lib "eagle-import") (part "RSPRO-1MM-TERMINAL-POST-2622034"))
    )
    (comp (ref "TP_VCM")
      (value "RSPRO-1MM-TERMINAL-POST-2622034")
      (footprint "eagle-import:RSPRO-1MM-TERMINAL-POST-2622034")
      (libsource (lib "eagle-import") (part "RSPRO-1MM-TERMINAL-POST-2622034"))
    )
    (comp (ref "TP_VREF_2V5")
      (value "RSPRO-1MM-TERMINAL-POST-2622034")
      (footprint "eagle-import:RSPRO-1MM-TERMINAL-POST-2622034")
      (libsource (lib "eagle-import") (part "RSPRO-1MM-TERMINAL-POST-2622034"))
    )
  )
  (nets
    (net (code "1") (name "+3V3") (class "Default")
      (node (ref "ADC") (pin "35") (pinfunction "IOVDD_35") (pintype "power_in"))
      (node (ref "ADC") (pin "56") (pinfunction "FORMAT0_56") (pintype "input"))
      (node (ref "ADC") (pin "57") (pinfunction "~{PIN}/SPI_57") (pintype "input"))
      (node (ref "C10") (pin "1") (pinfunction "1_1") (pintype "passive"))
      (node (ref "C11") (pin "1") (pinfunction "1_1") (pintype "passive"))
      (node (ref "C26") (pin "2") (pinfunction "2_2") (pintype "passive"))
      (node (ref "C5") (pin "+") (pinfunction "+_+") (pintype "passive"))
      (node (ref "C65") (pin "1") (pinfunction "1_1") (pintype "passive"))
      (node (ref "C66") (pin "1") (pinfunction "1_1") (pintype "passive"))
      (node (ref "C9") (pin "1") (pinfunction "1_1") (pintype "passive"))
      (node (ref "IC1") (pin "2") (pinfunction "OUT_2") (pintype "passive"))
      (node (ref "IC1") (pin "TAB") (pinfunction "OUT1_TAB") (pintype "passive"))
      (node (ref "IC11") (pin "16") (pinfunction "VCC_16") (pintype "power_in"))
      (node (ref "LED_+3.3V") (pin "A") (pinfunction "A_A") (pintype "passive"))
      (node (ref "OSC1") (pin "1") (pinfunction "~{ST}_1") (pintype "bidirectional"))
      (node (ref "OSC1") (pin "4") (pinfunction "VCC_4") (pintype "bidirectional"))
      (node (ref "R3") (pin "1") (pinfunction "1_1") (pintype "passive"))
      (node (ref "RD") (pin "1") (pinfunction "VCC_1") (pintype "power_in"))
      (node (ref "RD") (pin "15") (pinfunction "COM_15") (pintype "input"))
      (node (ref "RD") (pin "2") (pinfunction "~{SET}_2") (pintype "input"))
    )
    (net (code "2") (name "+5V") (class "Default")
      (node (ref "C1") (pin "+") (pinfunction "+_+") (pintype "passive"))
      (node (ref "C4") (pin "+") (pinfunction "+_+") (pintype "passive"))
      (node (ref "C63") (pin "1") (pinfunction "1_1") (pintype "passive"))
      (node (ref "C64") (pin "1") (pinfunction "1_1") (pintype "passive"))
      (node (ref "CON_BACKPLANE") (pin "1") (pinfunction "1_1") (pintype "bidirectional"))
      (node (ref "CON_BACKPLANE") (pin "2") (pinfunction "2_2") (pintype "bidirectional"))
      (node (ref "IC1") (pin "3") (pinfunction "IN_3") (pintype "input"))
      (node (ref "R27") (pin "2") (pinfunction "2_2") (pintype "passive"))
      (node (ref "R28") (pin "2") (pinfunction "2_2") (pintype "passive"))
      (node (ref "R29") (pin "2") (pinfunction "2_2") (pintype "passive"))
      (node (ref "R30") (pin "2") (pinfunction "2_2") (pintype "passive"))
      (node (ref "RELAY1") (pin "6") (pinfunction "6_6") (pintype "passive"))
      (node (ref "RELAY2") (pin "6") (pinfunction "6_6") (pintype "passive"))
    )
    (net (code "3") (name "+5V_ADC") (class "Default")
      (node (ref "ADC") (pin "4") (pinfunction "AVDD1A_4") (pintype "power_in"))
      (node (ref "ADC") (pin "45") (pinfunction "AVDD1B_45") (pintype "passive"))
      (node (ref "ADC") (pin "53") (pinfunction "AVDD2B_53") (pintype "power_in"))
      (node (ref "ADC") (pin "60") (pinfunction "AVDD2A_60") (pintype "power_in"))
      (node (ref "C12") (pin "1") (pinfunction "1_1") (pintype "passive"))
      (node (ref "C13") (pin "1") (pinfunction "1_1") (pintype "passive"))
      (node (ref "C14") (pin "1") (pinfunction "1_1") (pintype "passive"))
      (node (ref "C15") (pin "1") (pinfunction "1_1") (pintype "passive"))
      (node (ref "C16") (pin "1") (pinfunction "1_1") (pintype "passive"))
      (node (ref "C17") (pin "1") (pinfunction "1_1") (pintype "passive"))
      (node (ref "C18") (pin "1") (pinfunction "1_1") (pintype "passive"))
      (node (ref "C19") (pin "1") (pinfunction "1_1") (pintype "passive"))
      (node (ref "C8") (pin "+") (pinfunction "+_+") (pintype "passive"))
      (node (ref "IC2") (pin "2") (pinfunction "OUT_2") (pintype "passive"))
      (node (ref "IC2") (pin "TAB") (pinfunction "OUT1_TAB") (pintype "passive"))
      (node (ref "LED_+5V_ADC") (pin "A") (pinfunction "A_A") (pintype "passive"))
      (node (ref "SJ3") (pin "1") (pinfunction "1_1") (pintype "passive"))
    )
    (net (code "4") (name "+5V_FRONTEND") (class "Default")
      (node (ref "C41") (pin "2") (pinfunction "2_2") (pintype "passive"))
      (node (ref "C42") (pin "2") (pinfunction "2_2") (pintype "passive"))
      (node (ref "C43") (pin "2") (pinfunction "2_2") (pintype "passive"))
      (node (ref "C44") (pin "2") (pinfunction "2_2") (pintype "passive"))
      (node (ref "C48") (pin "+") (pinfunction "+_+") (pintype "passive"))
      (node (ref "C57") (pin "2") (pinfunction "2_2") (pintype "passive"))
      (node (ref "C59") (pin "2") (pinfunction "2_2") (pintype "passive"))
      (node (ref "IC10") (pin "7") (pinfunction "V+_7") (pintype "power_in"))
      (node (ref "IC5") (pin "12") (pinfunction "~{DISABLE}_12") (pintype "input"))
      (node (ref "IC5") (pin "5") (pinfunction "MODE_5") (pintype "input"))
      (node (ref "IC5") (pin "6") (pinfunction "+VS_6") (pintype "power_in"))
      (node (ref "IC5") (pin "7") (pinfunction "+VS_7") (pintype "power_in"))
      (node (ref "IC5") (pin "8") (pinfunction "+VCLAMP_8") (pintype "power_in"))
      (node (ref "IC6") (pin "12") (pinfunction "~{DISABLE}_12") (pintype "input"))
      (node (ref "IC6") (pin "5") (pinfunction "MODE_5") (pintype "input"))
      (node (ref "IC6") (pin "6") (pinfunction "+VS_6") (pintype "power_in"))
      (node (ref "IC6") (pin "7") (pinfunction "+VS_7") (pintype "power_in"))
      (node (ref "IC6") (pin "8") (pinfunction "+VCLAMP_8") (pintype "power_in"))
      (node (ref "IC7") (pin "2") (pinfunction "OUT_2") (pintype "passive"))
      (node (ref "IC7") (pin "TAB") (pinfunction "OUT1_TAB") (pintype "passive"))
      (node (ref "IC9") (pin "7") (pinfunction "V+_7") (pintype "power_in"))
      (node (ref "LED_+5V_FRONTEND") (pin "A") (pinfunction "A_A") (pintype "passive"))
    )
    (net (code "5") (name "+12V") (class "Default")
      (node (ref "C2") (pin "+") (pinfunction "+_+") (pintype "passive"))
      (node (ref "C29") (pin "2") (pinfunction "2_2") (pintype "passive"))
      (node (ref "C30") (pin "2") (pinfunction "2_2") (pintype "passive"))
      (node (ref "C33") (pin "2") (pinfunction "2_2") (pintype "passive"))
      (node (ref "C34") (pin "2") (pinfunction "2_2") (pintype "passive"))
      (node (ref "C45") (pin "2") (pinfunction "2_2") (pintype "passive"))
      (node (ref "C46") (pin "+") (pinfunction "+_+") (pintype "passive"))
      (node (ref "C52") (pin "2") (pinfunction "2_2") (pintype "passive"))
      (node (ref "C6") (pin "+") (pinfunction "+_+") (pintype "passive"))
      (node (ref "CON_BACKPLANE") (pin "5") (pinfunction "5_5") (pintype "bidirectional"))
      (node (ref "IC12") (pin "2") (pinfunction "VIN_2") (pintype "bidirectional"))
      (node (ref "IC3") (pin "2") (pinfunction "VIN_2") (pintype "bidirectional"))
      (node (ref "IC4") (pin "6") (pinfunction "V+_6") (pintype "bidirectional"))
      (node (ref "L1") (pin "1") (pinfunction "1_1") (pintype "passive"))
      (node (ref "L2") (pin "1") (pinfunction "1_1") (pintype "passive"))
    )
    (net (code "6") (name "-5V_FRONTEND") (class "Default")
      (node (ref "C51") (pin "-") (pinfunction "-_-") (pintype "passive"))
      (node (ref "C58") (pin "1") (pinfunction "1_1") (pintype "passive"))
      (node (ref "C60") (pin "1") (pinfunction "1_1") (pintype "passive"))
      (node (ref "IC10") (pin "4") (pinfunction "V-_4") (pintype "power_in"))
      (node (ref "IC8") (pin "3") (pinfunction "VOUT_3") (pintype "bidirectional"))
      (node (ref "IC9") (pin "4") (pinfunction "V-_4") (pintype "power_in"))
      (node (ref "R24") (pin "2") (pinfunction "2_2") (pintype "passive"))
    )
    (net (code "7") (name "-12V") (class "Default")
      (node (ref "C3") (pin "-") (pinfunction "-_-") (pintype "passive"))
      (node (ref "C49") (pin "-") (pinfunction "-_-") (pintype "passive"))
      (node (ref "CON_BACKPLANE") (pin "6") (pinfunction "6_6") (pintype "bidirectional"))
      (node (ref "L3") (pin "2") (pinfunction "2_2") (pintype "passive"))
    )
    (net (code "8") (name "ADC_AIN0_N") (class "Default")
      (node (ref "ADC") (pin "63") (pinfunction "AIN0-_63") (pintype "input"))
      (node (ref "C37") (pin "2") (pinfunction "2_2") (pintype "passive"))
      (node (ref "R11") (pin "1") (pinfunction "1_1") (pintype "passive"))
    )
    (net (code "9") (name "ADC_AIN0_P") (class "Default")
      (node (ref "ADC") (pin "64") (pinfunction "AIN0+_64") (pintype "input"))
      (node (ref "C36") (pin "1") (pinfunction "1_1") (pintype "passive"))
      (node (ref "R10") (pin "1") (pinfunction "1_1") (pintype "passive"))
    )
    (net (code "10") (name "ADC_AIN1_N") (class "Default")
      (node (ref "ADC") (pin "1") (pinfunction "AIN1-_1") (pintype "input"))
      (node (ref "C39") (pin "2") (pinfunction "2_2") (pintype "passive"))
      (node (ref "R13") (pin "1") (pinfunction "1_1") (pintype "passive"))
    )
    (net (code "11") (name "ADC_AIN1_P") (class "Default")
      (node (ref "ADC") (pin "2") (pinfunction "AIN1+_2") (pintype "input"))
      (node (ref "C38") (pin "1") (pinfunction "1_1") (pintype "passive"))
      (node (ref "R12") (pin "1") (pinfunction "1_1") (pintype "passive"))
    )
    (net (code "12") (name "ADC_MCLK") (class "Default")
      (node (ref "ADC") (pin "32") (pinfunction "XTAL2/MCLK_32") (pintype "input"))
      (node (ref "OSC1") (pin "3") (pinfunction "OUT_3") (pintype "bidirectional"))
    )
    (net (code "13") (name "ADC_NRESET") (class "Default")
      (node (ref "ADC") (pin "30") (pinfunction "~{RESET}_30") (pintype "input"))
      (node (ref "IC11") (pin "4") (pinfunction "P0_4") (pintype "bidirectional"))
      (node (ref "TP_ADC_NRESET") (pin "P$1") (pinfunction "P$1_P$1") (pintype "bidirectional"))
    )
    (net (code "14") (name "ADC_REF") (class "Default")
      (node (ref "ADC") (pin "43") (pinfunction "REF2+_43") (pintype "input"))
      (node (ref "ADC") (pin "6") (pinfunction "REF1+_6") (pintype "input"))
      (node (ref "C27") (pin "1") (pinfunction "1_1") (pintype "passive"))
      (node (ref "C28") (pin "1") (pinfunction "1_1") (pintype "passive"))
      (node (ref "SJ3") (pin "2") (pinfunction "2_2") (pintype "passive"))
    )
    (net (code "15") (name "BITE_PS_+5V_CURRENT") (class "Default")
      (node (ref "CON_BACKPLANE") (pin "9") (pinfunction "9_9") (pintype "bidirectional"))
    )
    (net (code "16") (name "BITE_PS_5V_TS1") (class "Default")
      (node (ref "CON_BACKPLANE") (pin "11") (pinfunction "11_11") (pintype "bidirectional"))
    )
    (net (code "17") (name "BITE_PS_5V_TS2") (class "Default")
      (node (ref "CON_BACKPLANE") (pin "12") (pinfunction "12_12") (pintype "bidirectional"))
    )
    (net (code "18") (name "BITE_PS_12V_TS1") (class "Default")
      (node (ref "CON_BACKPLANE") (pin "13") (pinfunction "13_13") (pintype "bidirectional"))
    )
    (net (code "19") (name "BITE_PS_12V_TS2") (class "Default")
      (node (ref "CON_BACKPLANE") (pin "14") (pinfunction "14_14") (pintype "bidirectional"))
    )
    (net (code "20") (name "EXT_REF") (class "Default")
      (node (ref "SJ2") (pin "2") (pinfunction "2_2") (pintype "passive"))
      (node (ref "SJ3") (pin "3") (pinfunction "3_3") (pintype "passive"))
    )
    (net (code "21") (name "GND") (class "Default")
      (node (ref "ADC") (pin "10") (pinfunction "AVSS10_10") (pintype "power_in"))
      (node (ref "ADC") (pin "3") (pinfunction "AVSS1A_3") (pintype "power_in"))
      (node (ref "ADC") (pin "31") (pinfunction "XTAL1_31") (pintype "input"))
      (node (ref "ADC") (pin "33") (pinfunction "DGND33_33") (pintype "power_in"))
      (node (ref "ADC") (pin "39") (pinfunction "AVSS39_39") (pintype "power_in"))
      (node (ref "ADC") (pin "40") (pinfunction "AVSS40_40") (pintype "power_in"))
      (node (ref "ADC") (pin "41") (pinfunction "AVSS41_41") (pintype "power_in"))
      (node (ref "ADC") (pin "42") (pinfunction "AVSS42_42") (pintype "power_in"))
      (node (ref "ADC") (pin "44") (pinfunction "REF2-_44") (pintype "input"))
      (node (ref "ADC") (pin "46") (pinfunction "AVSS1B_46") (pintype "passive"))
      (node (ref "ADC") (pin "47") (pinfunction "AIN3+_47") (pintype "input"))
      (node (ref "ADC") (pin "48") (pinfunction "AIN3-_48") (pintype "input"))
      (node (ref "ADC") (pin "49") (pinfunction "AIN2+_49") (pintype "input"))
      (node (ref "ADC") (pin "5") (pinfunction "REF1-_5") (pintype "input"))
      (node (ref "ADC") (pin "50") (pinfunction "AIN2-_50") (pintype "input"))
      (node (ref "ADC") (pin "51") (pinfunction "AVSS2B_51") (pintype "power_in"))
      (node (ref "ADC") (pin "54") (pinfunction "AVSS54_54") (pintype "power_in"))
      (node (ref "ADC") (pin "55") (pinfunction "DGND55_55") (pintype "power_in"))
      (node (ref "ADC") (pin "58") (pinfunction "CLK_SEL_58") (pintype "input"))
      (node (ref "ADC") (pin "62") (pinfunction "AVSS2A_62") (pintype "power_in"))
      (node (ref "ADC") (pin "7") (pinfunction "AVSS7_7") (pintype "power_in"))
      (node (ref "ADC") (pin "8") (pinfunction "AVSS8_8") (pintype "power_in"))
      (node (ref "ADC") (pin "9") (pinfunction "AVSS9_9") (pintype "power_in"))
      (node (ref "C1") (pin "-") (pinfunction "-_-") (pintype "passive"))
      (node (ref "C10") (pin "2") (pinfunction "2_2") (pintype "passive"))
      (node (ref "C11") (pin "2") (pinfunction "2_2") (pintype "passive"))
      (node (ref "C12") (pin "2") (pinfunction "2_2") (pintype "passive"))
      (node (ref "C13") (pin "2") (pinfunction "2_2") (pintype "passive"))
      (node (ref "C14") (pin "2") (pinfunction "2_2") (pintype "passive"))
      (node (ref "C15") (pin "2") (pinfunction "2_2") (pintype "passive"))
      (node (ref "C16") (pin "2") (pinfunction "2_2") (pintype "passive"))
      (node (ref "C17") (pin "2") (pinfunction "2_2") (pintype "passive"))
      (node (ref "C18") (pin "2") (pinfunction "2_2") (pintype "passive"))
      (node (ref "C19") (pin "2") (pinfunction "2_2") (pintype "passive"))
      (node (ref "C2") (pin "-") (pinfunction "-_-") (pintype "passive"))
      (node (ref "C20") (pin "2") (pinfunction "2_2") (pintype "passive"))
      (node (ref "C21") (pin "2") (pinfunction "2_2") (pintype "passive"))
      (node (ref "C22") (pin "2") (pinfunction "2_2") (pintype "passive"))
      (node (ref "C23") (pin "2") (pinfunction "2_2") (pintype "passive"))
      (node (ref "C24") (pin "2") (pinfunction "2_2") (pintype "passive"))
      (node (ref "C25") (pin "2") (pinfunction "2_2") (pintype "passive"))
      (node (ref "C26") (pin "1") (pinfunction "1_1") (pintype "passive"))
      (node (ref "C27") (pin "2") (pinfunction "2_2") (pintype "passive"))
      (node (ref "C28") (pin "2") (pinfunction "2_2") (pintype "passive"))
      (node (ref "C29") (pin "1") (pinfunction "1_1") (pintype "passive"))
      (node (ref "C3") (pin "+") (pinfunction "+_+") (pintype "passive"))
      (node (ref "C30") (pin "1") (pinfunction "1_1") (pintype "passive"))
      (node (ref "C31") (pin "1") (pinfunction "1_1") (pintype "passive"))
      (node (ref "C32") (pin "1") (pinfunction "1_1") (pintype "passive"))
      (node (ref "C33") (pin "1") (pinfunction "1_1") (pintype "passive"))
      (node (ref "C34") (pin "1") (pinfunction "1_1") (pintype "passive"))
      (node (ref "C36") (pin "2") (pinfunction "2_2") (pintype "passive"))
      (node (ref "C37") (pin "1") (pinfunction "1_1") (pintype "passive"))
      (node (ref "C38") (pin "2") (pinfunction "2_2") (pintype "passive"))
      (node (ref "C39") (pin "1") (pinfunction "1_1") (pintype "passive"))
      (node (ref "C4") (pin "-") (pinfunction "-_-") (pintype "passive"))
      (node (ref "C40") (pin "2") (pinfunction "2_2") (pintype "passive"))
      (node (ref "C41") (pin "1") (pinfunction "1_1") (pintype "passive"))
      (node (ref "C42") (pin "1") (pinfunction "1_1") (pintype "passive"))
      (node (ref "C43") (pin "1") (pinfunction "1_1") (pintype "passive"))
      (node (ref "C44") (pin "1") (pinfunction "1_1") (pintype "passive"))
      (node (ref "C45") (pin "1") (pinfunction "1_1") (pintype "passive"))
      (node (ref "C46") (pin "-") (pinfunction "-_-") (pintype "passive"))
      (node (ref "C47") (pin "-") (pinfunction "-_-") (pintype "passive"))
      (node (ref "C48") (pin "-") (pinfunction "-_-") (pintype "passive"))
      (node (ref "C49") (pin "+") (pinfunction "+_+") (pintype "passive"))
      (node (ref "C5") (pin "-") (pinfunction "-_-") (pintype "passive"))
      (node (ref "C50") (pin "+") (pinfunction "+_+") (pintype "passive"))
      (node (ref "C51") (pin "+") (pinfunction "+_+") (pintype "passive"))
      (node (ref "C52") (pin "1") (pinfunction "1_1") (pintype "passive"))
      (node (ref "C57") (pin "1") (pinfunction "1_1") (pintype "passive"))
      (node (ref "C58") (pin "2") (pinfunction "2_2") (pintype "passive"))
      (node (ref "C59") (pin "1") (pinfunction "1_1") (pintype "passive"))
      (node (ref "C6") (pin "-") (pinfunction "-_-") (pintype "passive"))
      (node (ref "C60") (pin "2") (pinfunction "2_2") (pintype "passive"))
      (node (ref "C61") (pin "2") (pinfunction "2_2") (pintype "passive"))
      (node (ref "C62") (pin "2") (pinfunction "2_2") (pintype "passive"))
      (node (ref "C63") (pin "2") (pinfunction "2_2") (pintype "passive"))
      (node (ref "C64") (pin "2") (pinfunction "2_2") (pintype "passive"))
      (node (ref "C65") (pin "2") (pinfunction "2_2") (pintype "passive"))
      (node (ref "C66") (pin "2") (pinfunction "2_2") (pintype "passive"))
      (node (ref "C67") (pin "1") (pinfunction "1_1") (pintype "passive"))
      (node (ref "C7") (pin "-") (pinfunction "-_-") (pintype "passive"))
      (node (ref "C8") (pin "-") (pinfunction "-_-") (pintype "passive"))
      (node (ref "C9") (pin "2") (pinfunction "2_2") (pintype "passive"))
      (node (ref "CON_BACKPLANE") (pin "10") (pinfunction "10_10") (pintype "bidirectional"))
      (node (ref "CON_BACKPLANE") (pin "15") (pinfunction "15_15") (pintype "bidirectional"))
      (node (ref "CON_BACKPLANE") (pin "25") (pinfunction "25_25") (pintype "bidirectional"))
      (node (ref "CON_BACKPLANE") (pin "26") (pinfunction "26_26") (pintype "bidirectional"))
      (node (ref "CON_BACKPLANE") (pin "27") (pinfunction "27_27") (pintype "bidirectional"))
      (node (ref "CON_BACKPLANE") (pin "28") (pinfunction "28_28") (pintype "bidirectional"))
      (node (ref "CON_BACKPLANE") (pin "29") (pinfunction "29_29") (pintype "bidirectional"))
      (node (ref "CON_BACKPLANE") (pin "3") (pinfunction "3_3") (pintype "bidirectional"))
      (node (ref "CON_BACKPLANE") (pin "30") (pinfunction "30_30") (pintype "bidirectional"))
      (node (ref "CON_BACKPLANE") (pin "31") (pinfunction "31_31") (pintype "bidirectional"))
      (node (ref "CON_BACKPLANE") (pin "32") (pinfunction "32_32") (pintype "bidirectional"))
      (node (ref "CON_BACKPLANE") (pin "4") (pinfunction "4_4") (pintype "bidirectional"))
      (node (ref "CON_BACKPLANE") (pin "7") (pinfunction "7_7") (pintype "bidirectional"))
      (node (ref "CON_BACKPLANE") (pin "8") (pinfunction "8_8") (pintype "bidirectional"))
      (node (ref "CON_EXT_CH1") (pin "G1") (pinfunction "G_G1") (pintype "passive"))
      (node (ref "CON_EXT_CH1") (pin "G2") (pinfunction "G_G2") (pintype "passive"))
      (node (ref "CON_EXT_CH1") (pin "G3") (pinfunction "G_G3") (pintype "passive"))
      (node (ref "CON_EXT_CH1") (pin "G4") (pinfunction "G_G4") (pintype "passive"))
      (node (ref "CON_EXT_CH2") (pin "G1") (pinfunction "G_G1") (pintype "passive"))
      (node (ref "CON_EXT_CH2") (pin "G2") (pinfunction "G_G2") (pintype "passive"))
      (node (ref "CON_EXT_CH2") (pin "G3") (pinfunction "G_G3") (pintype "passive"))
      (node (ref "CON_EXT_CH2") (pin "G4") (pinfunction "G_G4") (pintype "passive"))
      (node (ref "CON_INT_CH1") (pin "G1") (pinfunction "GND_G1") (pintype "passive"))
      (node (ref "CON_INT_CH1") (pin "G2") (pinfunction "GND_G2") (pintype "passive"))
      (node (ref "CON_INT_CH2") (pin "G1") (pinfunction "GND_G1") (pintype "passive"))
      (node (ref "CON_INT_CH2") (pin "G2") (pinfunction "GND_G2") (pintype "passive"))
      (node (ref "IC1") (pin "1") (pinfunction "GND_1") (pintype "input"))
      (node (ref "IC11") (pin "1") (pinfunction "A0_1") (pintype "bidirectional"))
      (node (ref "IC11") (pin "2") (pinfunction "A1_2") (pintype "bidirectional"))
      (node (ref "IC11") (pin "3") (pinfunction "A2_3") (pintype "bidirectional"))
      (node (ref "IC11") (pin "8") (pinfunction "GND_8") (pintype "power_in"))
      (node (ref "IC12") (pin "4") (pinfunction "GND_4") (pintype "bidirectional"))
      (node (ref "IC2") (pin "1") (pinfunction "GND_1") (pintype "input"))
      (node (ref "IC3") (pin "4") (pinfunction "GND_4") (pintype "bidirectional"))
      (node (ref "IC4") (pin "2") (pinfunction "V-_2") (pintype "bidirectional"))
      (node (ref "IC5") (pin "13") (pinfunction "-VCLAMP_13") (pintype "power_in"))
      (node (ref "IC5") (pin "14") (pinfunction "-VS_14") (pintype "power_in"))
      (node (ref "IC5") (pin "15") (pinfunction "-VS_15") (pintype "power_in"))
      (node (ref "IC5") (pin "16") (pinfunction "DGND_16") (pintype "power_in"))
      (node (ref "IC5") (pin "17") (pinfunction "EP_17") (pintype "power_in"))
      (node (ref "IC6") (pin "13") (pinfunction "-VCLAMP_13") (pintype "power_in"))
      (node (ref "IC6") (pin "14") (pinfunction "-VS_14") (pintype "power_in"))
      (node (ref "IC6") (pin "15") (pinfunction "-VS_15") (pintype "power_in"))
      (node (ref "IC6") (pin "16") (pinfunction "DGND_16") (pintype "power_in"))
      (node (ref "IC6") (pin "17") (pinfunction "EP_17") (pintype "power_in"))
      (node (ref "IC7") (pin "1") (pinfunction "GND_1") (pintype "input"))
      (node (ref "IC8") (pin "1") (pinfunction "GND_1") (pintype "bidirectional"))
      (node (ref "LED_-5V_FRONTEND") (pin "A") (pinfunction "A_A") (pintype "passive"))
      (node (ref "LED_SHORT_CH1") (pin "-") (pinfunction "C_-") (pintype "passive"))
      (node (ref "LED_SHORT_CH2") (pin "-") (pinfunction "C_-") (pintype "passive"))
      (node (ref "OSC1") (pin "2") (pinfunction "GND_2") (pintype "bidirectional"))
      (node (ref "R1") (pin "2") (pinfunction "2_2") (pintype "passive"))
      (node (ref "R18") (pin "2") (pinfunction "2_2") (pintype "passive"))
      (node (ref "R2") (pin "2") (pinfunction "2_2") (pintype "passive"))
      (node (ref "R22") (pin "2") (pinfunction "2_2") (pintype "passive"))
      (node (ref "R23") (pin "2") (pinfunction "2_2") (pintype "passive"))
      (node (ref "R33") (pin "1") (pinfunction "1_1") (pintype "passive"))
      (node (ref "R34") (pin "1") (pinfunction "1_1") (pintype "passive"))
      (node (ref "R4") (pin "1") (pinfunction "1_1") (pintype "passive"))
      (node (ref "R5") (pin "1") (pinfunction "1_1") (pintype "passive"))
      (node (ref "RD") (pin "12") (pinfunction "PGND_12") (pintype "power_in"))
      (node (ref "RD") (pin "18") (pinfunction "PGND_18") (pintype "power_in"))
      (node (ref "RD") (pin "21") (pinfunction "GND_21") (pintype "power_in"))
      (node (ref "RD") (pin "9") (pinfunction "GND_9") (pintype "power_in"))
      (node (ref "RELAY1") (pin "4") (pinfunction "4_4") (pintype "passive"))
      (node (ref "RELAY2") (pin "4") (pinfunction "4_4") (pintype "passive"))
      (node (ref "TP_GND1") (pin "P$1") (pinfunction "P$1_P$1") (pintype "bidirectional"))
      (node (ref "TP_GND2") (pin "P$1") (pinfunction "P$1_P$1") (pintype "bidirectional"))
      (node (ref "TP_GND3") (pin "P$1") (pinfunction "P$1_P$1") (pintype "bidirectional"))
      (node (ref "TP_GND4") (pin "P$1") (pinfunction "P$1_P$1") (pintype "bidirectional"))
    )
    (net (code "22") (name "I2C_NINT") (class "Default")
      (node (ref "CON_BACKPLANE") (pin "22") (pinfunction "22_22") (pintype "bidirectional"))
      (node (ref "IC11") (pin "13") (pinfunction "~{INT}_13") (pintype "bidirectional"))
      (node (ref "TP_I2C_NINT") (pin "P$1") (pinfunction "P$1_P$1") (pintype "bidirectional"))
    )
    (net (code "23") (name "I2C_SCL") (class "Default")
      (node (ref "CON_BACKPLANE") (pin "24") (pinfunction "24_24") (pintype "bidirectional"))
      (node (ref "IC11") (pin "14") (pinfunction "SCL_14") (pintype "bidirectional"))
      (node (ref "TP_I2C_SCL") (pin "P$1") (pinfunction "P$1_P$1") (pintype "bidirectional"))
    )
    (net (code "24") (name "I2C_SDA") (class "Default")
      (node (ref "CON_BACKPLANE") (pin "23") (pinfunction "23_23") (pintype "bidirectional"))
      (node (ref "IC11") (pin "15") (pinfunction "SDA_15") (pintype "bidirectional"))
      (node (ref "TP_I2C_SDA") (pin "P$1") (pinfunction "P$1_P$1") (pintype "bidirectional"))
    )
    (net (code "25") (name "Net-(ADC-DIN)") (class "Default")
      (node (ref "ADC") (pin "21") (pinfunction "DIN_21") (pintype "power_in"))
      (node (ref "R5") (pin "2") (pinfunction "2_2") (pintype "passive"))
    )
    (net (code "26") (name "Net-(ADC-DNC{slash}DGND)") (class "Default")
      (node (ref "ADC") (pin "20") (pinfunction "DNC/DGND_20") (pintype "power_in"))
      (node (ref "R4") (pin "2") (pinfunction "2_2") (pintype "passive"))
    )
    (net (code "27") (name "Net-(ADC-DREGCAP)") (class "Default")
      (node (ref "ADC") (pin "34") (pinfunction "DREGCAP_34") (pintype "output"))
      (node (ref "C20") (pin "1") (pinfunction "1_1") (pintype "passive"))
      (node (ref "C21") (pin "1") (pinfunction "1_1") (pintype "passive"))
    )
    (net (code "28") (name "Net-(ADC-REGCAPA)") (class "Default")
      (node (ref "ADC") (pin "61") (pinfunction "REGCAPA_61") (pintype "output"))
      (node (ref "C24") (pin "1") (pinfunction "1_1") (pintype "passive"))
      (node (ref "C25") (pin "1") (pinfunction "1_1") (pintype "passive"))
    )
    (net (code "29") (name "Net-(ADC-REGCAPB)") (class "Default")
      (node (ref "ADC") (pin "52") (pinfunction "REGCAPB_52") (pintype "output"))
      (node (ref "C22") (pin "1") (pinfunction "1_1") (pintype "passive"))
      (node (ref "C23") (pin "1") (pinfunction "1_1") (pintype "passive"))
    )
    (net (code "30") (name "Net-(ADC-VCM)") (class "Default")
      (node (ref "ADC") (pin "59") (pinfunction "VCM_59") (pintype "output"))
      (node (ref "R14") (pin "1") (pinfunction "1_1") (pintype "passive"))
    )
    (net (code "31") (name "Net-(ADC-~{START})") (class "Default")
      (node (ref "ADC") (pin "37") (pinfunction "~{START}_37") (pintype "input"))
      (node (ref "R3") (pin "2") (pinfunction "2_2") (pintype "passive"))
    )
    (net (code "32") (name "Net-(ADC-~{SYNC_IN})") (class "Default")
      (node (ref "ADC") (pin "36") (pinfunction "~{SYNC_IN}_36") (pintype "input"))
      (node (ref "ADC") (pin "38") (pinfunction "~{SYNC_OUT}_38") (pintype "output"))
    )
    (net (code "33") (name "Net-(C35-Pad1)") (class "Default")
      (node (ref "C35") (pin "1") (pinfunction "1_1") (pintype "passive"))
      (node (ref "R7") (pin "1") (pinfunction "1_1") (pintype "passive"))
    )
    (net (code "34") (name "Net-(CON_INT_CH1-SIG)") (class "Default")
      (node (ref "CON_EXT_CH1") (pin "S") (pinfunction "S_S") (pintype "passive"))
      (node (ref "CON_INT_CH1") (pin "S") (pinfunction "SIG_S") (pintype "passive"))
      (node (ref "RELAY1") (pin "2") (pinfunction "2_2") (pintype "passive"))
    )
    (net (code "35") (name "Net-(CON_INT_CH2-SIG)") (class "Default")
      (node (ref "CON_EXT_CH2") (pin "S") (pinfunction "S_S") (pintype "passive"))
      (node (ref "CON_INT_CH2") (pin "S") (pinfunction "SIG_S") (pintype "passive"))
      (node (ref "RELAY2") (pin "2") (pinfunction "2_2") (pintype "passive"))
    )
    (net (code "36") (name "Net-(IC2-IN)") (class "Default")
      (node (ref "C7") (pin "+") (pinfunction "+_+") (pintype "passive"))
      (node (ref "IC2") (pin "3") (pinfunction "IN_3") (pintype "input"))
      (node (ref "L1") (pin "2") (pinfunction "2_2") (pintype "passive"))
    )
    (net (code "37") (name "Net-(IC4-+)") (class "Default")
      (node (ref "C32") (pin "2") (pinfunction "2_2") (pintype "passive"))
      (node (ref "IC4") (pin "3") (pinfunction "+_3") (pintype "bidirectional"))
      (node (ref "R6") (pin "2") (pinfunction "2_2") (pintype "passive"))
    )
    (net (code "38") (name "Net-(IC4--)") (class "Default")
      (node (ref "C35") (pin "2") (pinfunction "2_2") (pintype "passive"))
      (node (ref "IC4") (pin "4") (pinfunction "-_4") (pintype "bidirectional"))
      (node (ref "R8") (pin "1") (pinfunction "1_1") (pintype "passive"))
    )
    (net (code "39") (name "Net-(IC4-VOUT)") (class "Default")
      (node (ref "IC4") (pin "1") (pinfunction "VOUT_1") (pintype "bidirectional"))
      (node (ref "R7") (pin "2") (pinfunction "2_2") (pintype "passive"))
      (node (ref "R9") (pin "1") (pinfunction "1_1") (pintype "passive"))
    )
    (net (code "40") (name "Net-(IC5-+FB)") (class "Default")
      (node (ref "C54") (pin "1") (pinfunction "1_1") (pintype "passive"))
      (node (ref "IC5") (pin "4") (pinfunction "+FB_4") (pintype "input"))
      (node (ref "R16") (pin "1") (pinfunction "1_1") (pintype "passive"))
    )
    (net (code "41") (name "Net-(IC5-+IN)") (class "Default")
      (node (ref "C53") (pin "1") (pinfunction "1_1") (pintype "passive"))
      (node (ref "IC5") (pin "2") (pinfunction "+IN_2") (pintype "input"))
      (node (ref "R15") (pin "2") (pinfunction "2_2") (pintype "passive"))
      (node (ref "R17") (pin "1") (pinfunction "1_1") (pintype "passive"))
    )
    (net (code "42") (name "Net-(IC5-+OUT)") (class "Default")
      (node (ref "IC5") (pin "10") (pinfunction "+OUT_10") (pintype "output"))
      (node (ref "R10") (pin "2") (pinfunction "2_2") (pintype "passive"))
    )
    (net (code "43") (name "Net-(IC5--FB)") (class "Default")
      (node (ref "C53") (pin "2") (pinfunction "2_2") (pintype "passive"))
      (node (ref "IC5") (pin "1") (pinfunction "-FB_1") (pintype "input"))
      (node (ref "R15") (pin "1") (pinfunction "1_1") (pintype "passive"))
    )
    (net (code "44") (name "Net-(IC5--IN)") (class "Default")
      (node (ref "C54") (pin "2") (pinfunction "2_2") (pintype "passive"))
      (node (ref "IC5") (pin "3") (pinfunction "-IN_3") (pintype "input"))
      (node (ref "R16") (pin "2") (pinfunction "2_2") (pintype "passive"))
      (node (ref "R18") (pin "1") (pinfunction "1_1") (pintype "passive"))
    )
    (net (code "45") (name "Net-(IC5--OUT)") (class "Default")
      (node (ref "IC5") (pin "11") (pinfunction "-OUT_11") (pintype "output"))
      (node (ref "R11") (pin "2") (pinfunction "2_2") (pintype "passive"))
    )
    (net (code "46") (name "Net-(IC6-+FB)") (class "Default")
      (node (ref "C56") (pin "1") (pinfunction "1_1") (pintype "passive"))
      (node (ref "IC6") (pin "4") (pinfunction "+FB_4") (pintype "input"))
      (node (ref "R20") (pin "1") (pinfunction "1_1") (pintype "passive"))
    )
    (net (code "47") (name "Net-(IC6-+IN)") (class "Default")
      (node (ref "C55") (pin "1") (pinfunction "1_1") (pintype "passive"))
      (node (ref "IC6") (pin "2") (pinfunction "+IN_2") (pintype "input"))
      (node (ref "R19") (pin "2") (pinfunction "2_2") (pintype "passive"))
      (node (ref "R21") (pin "1") (pinfunction "1_1") (pintype "passive"))
    )
    (net (code "48") (name "Net-(IC6-+OUT)") (class "Default")
      (node (ref "IC6") (pin "10") (pinfunction "+OUT_10") (pintype "output"))
      (node (ref "R12") (pin "2") (pinfunction "2_2") (pintype "passive"))
    )
    (net (code "49") (name "Net-(IC6--FB)") (class "Default")
      (node (ref "C55") (pin "2") (pinfunction "2_2") (pintype "passive"))
      (node (ref "IC6") (pin "1") (pinfunction "-FB_1") (pintype "input"))
      (node (ref "R19") (pin "1") (pinfunction "1_1") (pintype "passive"))
    )
    (net (code "50") (name "Net-(IC6--IN)") (class "Default")
      (node (ref "C56") (pin "2") (pinfunction "2_2") (pintype "passive"))
      (node (ref "IC6") (pin "3") (pinfunction "-IN_3") (pintype "input"))
      (node (ref "R20") (pin "2") (pinfunction "2_2") (pintype "passive"))
      (node (ref "R22") (pin "1") (pinfunction "1_1") (pintype "passive"))
    )
    (net (code "51") (name "Net-(IC6--OUT)") (class "Default")
      (node (ref "IC6") (pin "11") (pinfunction "-OUT_11") (pintype "output"))
      (node (ref "R13") (pin "2") (pinfunction "2_2") (pintype "passive"))
    )
    (net (code "52") (name "Net-(IC7-IN)") (class "Default")
      (node (ref "C47") (pin "+") (pinfunction "+_+") (pintype "passive"))
      (node (ref "IC7") (pin "3") (pinfunction "IN_3") (pintype "input"))
      (node (ref "L2") (pin "2") (pinfunction "2_2") (pintype "passive"))
    )
    (net (code "53") (name "Net-(IC8-VIN)") (class "Default")
      (node (ref "C50") (pin "-") (pinfunction "-_-") (pintype "passive"))
      (node (ref "IC8") (pin "2") (pinfunction "VIN_2") (pintype "bidirectional"))
      (node (ref "L3") (pin "1") (pinfunction "1_1") (pintype "passive"))
    )
    (net (code "54") (name "Net-(IC9-+IN)") (class "Default")
      (node (ref "C61") (pin "1") (pinfunction "1_1") (pintype "passive"))
      (node (ref "IC9") (pin "3") (pinfunction "+IN_3") (pintype "input"))
      (node (ref "R25") (pin "1") (pinfunction "1_1") (pintype "passive"))
      (node (ref "R33") (pin "2") (pinfunction "2_2") (pintype "passive"))
    )
    (net (code "55") (name "Net-(IC9--IN)") (class "Default")
      (node (ref "IC9") (pin "2") (pinfunction "-IN_2") (pintype "input"))
      (node (ref "IC9") (pin "6") (pinfunction "OUT_6") (pintype "output"))
      (node (ref "R17") (pin "2") (pinfunction "2_2") (pintype "passive"))
      (node (ref "TP_FDA1_IN") (pin "P$1") (pinfunction "P$1_P$1") (pintype "bidirectional"))
    )
    (net (code "56") (name "Net-(IC10-+IN)") (class "Default")
      (node (ref "C62") (pin "1") (pinfunction "1_1") (pintype "passive"))
      (node (ref "IC10") (pin "3") (pinfunction "+IN_3") (pintype "input"))
      (node (ref "R26") (pin "1") (pinfunction "1_1") (pintype "passive"))
      (node (ref "R34") (pin "2") (pinfunction "2_2") (pintype "passive"))
    )
    (net (code "57") (name "Net-(IC10--IN)") (class "Default")
      (node (ref "IC10") (pin "2") (pinfunction "-IN_2") (pintype "input"))
      (node (ref "IC10") (pin "6") (pinfunction "OUT_6") (pintype "output"))
      (node (ref "R21") (pin "2") (pinfunction "2_2") (pintype "passive"))
      (node (ref "TP_FDA2_IN") (pin "P$1") (pinfunction "P$1_P$1") (pintype "bidirectional"))
    )
    (net (code "58") (name "Net-(LED_+3.3V-PadC)") (class "Default")
      (node (ref "LED_+3.3V") (pin "C") (pinfunction "C_C") (pintype "passive"))
      (node (ref "R1") (pin "1") (pinfunction "1_1") (pintype "passive"))
    )
    (net (code "59") (name "Net-(LED_+5V_ADC-PadC)") (class "Default")
      (node (ref "LED_+5V_ADC") (pin "C") (pinfunction "C_C") (pintype "passive"))
      (node (ref "R2") (pin "1") (pinfunction "1_1") (pintype "passive"))
    )
    (net (code "60") (name "Net-(LED_+5V_FRONTEND-PadC)") (class "Default")
      (node (ref "LED_+5V_FRONTEND") (pin "C") (pinfunction "C_C") (pintype "passive"))
      (node (ref "R23") (pin "1") (pinfunction "1_1") (pintype "passive"))
    )
    (net (code "61") (name "Net-(LED_-5V_FRONTEND-PadC)") (class "Default")
      (node (ref "LED_-5V_FRONTEND") (pin "C") (pinfunction "C_C") (pintype "passive"))
      (node (ref "R24") (pin "1") (pinfunction "1_1") (pintype "passive"))
    )
    (net (code "62") (name "Net-(LED_SHORT_CH1-A)") (class "Default")
      (node (ref "LED_SHORT_CH1") (pin "+") (pinfunction "A_+") (pintype "passive"))
      (node (ref "R31") (pin "2") (pinfunction "2_2") (pintype "passive"))
    )
    (net (code "63") (name "Net-(LED_SHORT_CH2-A)") (class "Default")
      (node (ref "LED_SHORT_CH2") (pin "+") (pinfunction "A_+") (pintype "passive"))
      (node (ref "R32") (pin "2") (pinfunction "2_2") (pintype "passive"))
    )
    (net (code "64") (name "Net-(R6-Pad1)") (class "Default")
      (node (ref "R6") (pin "1") (pinfunction "1_1") (pintype "passive"))
      (node (ref "SJ1") (pin "3") (pinfunction "3_3") (pintype "passive"))
    )
    (net (code "65") (name "Net-(R25-Pad2)") (class "Default")
      (node (ref "R25") (pin "2") (pinfunction "2_2") (pintype "passive"))
      (node (ref "RELAY1") (pin "3") (pinfunction "3_3") (pintype "passive"))
    )
    (net (code "66") (name "Net-(R26-Pad2)") (class "Default")
      (node (ref "R26") (pin "2") (pinfunction "2_2") (pintype "passive"))
      (node (ref "RELAY2") (pin "3") (pinfunction "3_3") (pintype "passive"))
    )
    (net (code "67") (name "Net-(R31-Pad1)") (class "Default")
      (node (ref "R31") (pin "1") (pinfunction "1_1") (pintype "passive"))
      (node (ref "RELAY1") (pin "5") (pinfunction "5_5") (pintype "passive"))
    )
    (net (code "68") (name "Net-(R32-Pad1)") (class "Default")
      (node (ref "R32") (pin "1") (pinfunction "1_1") (pintype "passive"))
      (node (ref "RELAY2") (pin "5") (pinfunction "5_5") (pintype "passive"))
    )
    (net (code "69") (name "Net-(SJ1-Pad1)") (class "Default")
      (node (ref "SJ1") (pin "1") (pinfunction "1_1") (pintype "passive"))
      (node (ref "SJ2") (pin "3") (pinfunction "3_3") (pintype "passive"))
    )
    (net (code "70") (name "RD_NRESET") (class "Default")
      (node (ref "IC11") (pin "7") (pinfunction "P3_7") (pintype "bidirectional"))
      (node (ref "RD") (pin "3") (pinfunction "~{RESET}_3") (pintype "input"))
      (node (ref "TP_RD_NRESET") (pin "P$1") (pinfunction "P$1_P$1") (pintype "bidirectional"))
    )
    (net (code "71") (name "RD_OUT1") (class "Default")
      (node (ref "R27") (pin "1") (pinfunction "1_1") (pintype "passive"))
      (node (ref "RD") (pin "20") (pinfunction "OUT1_20") (pintype "output"))
      (node (ref "RELAY1") (pin "1") (pinfunction "1_1") (pintype "passive"))
    )
    (net (code "72") (name "RD_OUT2") (class "Default")
      (node (ref "R28") (pin "1") (pinfunction "1_1") (pintype "passive"))
      (node (ref "RD") (pin "19") (pinfunction "OUT2_19") (pintype "output"))
      (node (ref "RELAY1") (pin "8") (pinfunction "8_8") (pintype "passive"))
    )
    (net (code "73") (name "RD_OUT3") (class "Default")
      (node (ref "R29") (pin "1") (pinfunction "1_1") (pintype "passive"))
      (node (ref "RD") (pin "17") (pinfunction "OUT3_17") (pintype "output"))
      (node (ref "RELAY2") (pin "1") (pinfunction "1_1") (pintype "passive"))
    )
    (net (code "74") (name "RD_OUT4") (class "Default")
      (node (ref "R30") (pin "1") (pinfunction "1_1") (pintype "passive"))
      (node (ref "RD") (pin "16") (pinfunction "OUT4_16") (pintype "output"))
      (node (ref "RELAY2") (pin "8") (pinfunction "8_8") (pintype "passive"))
    )
    (net (code "75") (name "RD_SPI_NCS") (class "Default")
      (node (ref "IC11") (pin "6") (pinfunction "P2_6") (pintype "bidirectional"))
      (node (ref "RD") (pin "4") (pinfunction "~{CS}_4") (pintype "input"))
      (node (ref "TP_RD_SPI_NCS") (pin "P$1") (pinfunction "P$1_P$1") (pintype "bidirectional"))
    )
    (net (code "76") (name "SPI_CONFIG_ADC_NCS") (class "Default")
      (node (ref "ADC") (pin "16") (pinfunction "ST0/~{CS}_16") (pintype "input"))
      (node (ref "IC11") (pin "5") (pinfunction "P1_5") (pintype "bidirectional"))
      (node (ref "TP_SPI_CONFIG_ADC_NCS") (pin "P$1") (pinfunction "P$1_P$1") (pintype "bidirectional"))
    )
    (net (code "77") (name "SPI_CONFIG_CLK") (class "Default")
      (node (ref "ADC") (pin "17") (pinfunction "SCLK_17") (pintype "input"))
      (node (ref "CON_BACKPLANE") (pin "21") (pinfunction "21_21") (pintype "bidirectional"))
      (node (ref "RD") (pin "6") (pinfunction "SCLK_6") (pintype "input"))
      (node (ref "TP_SPI_CONFIG_CLK") (pin "P$1") (pinfunction "P$1_P$1") (pintype "bidirectional"))
    )
    (net (code "78") (name "SPI_CONFIG_MISO") (class "Default")
      (node (ref "ADC") (pin "19") (pinfunction "DEC0/SDO_19") (pintype "output"))
      (node (ref "CON_BACKPLANE") (pin "19") (pinfunction "19_19") (pintype "bidirectional"))
      (node (ref "RD") (pin "7") (pinfunction "DOUT_7") (pintype "output"))
      (node (ref "TP_SPI_CONFIG_MISO") (pin "P$1") (pinfunction "P$1_P$1") (pintype "bidirectional"))
    )
    (net (code "79") (name "SPI_CONFIG_MOSI") (class "Default")
      (node (ref "ADC") (pin "18") (pinfunction "DEC1/SDI_18") (pintype "input"))
      (node (ref "CON_BACKPLANE") (pin "20") (pinfunction "20_20") (pintype "bidirectional"))
      (node (ref "RD") (pin "5") (pinfunction "DIN_5") (pintype "input"))
      (node (ref "TP_SPI_CONFIG_MOSI") (pin "P$1") (pinfunction "P$1_P$1") (pintype "bidirectional"))
    )
    (net (code "80") (name "SPI_DATA_CLK") (class "Default")
      (node (ref "ADC") (pin "28") (pinfunction "DCLK_28") (pintype "output"))
      (node (ref "CON_BACKPLANE") (pin "17") (pinfunction "17_17") (pintype "bidirectional"))
      (node (ref "TP_SPI_DATA_CLK") (pin "P$1") (pinfunction "P$1_P$1") (pintype "bidirectional"))
    )
    (net (code "81") (name "SPI_DATA_MOSI") (class "Default")
      (node (ref "ADC") (pin "27") (pinfunction "DOUT0_27") (pintype "output"))
      (node (ref "CON_BACKPLANE") (pin "18") (pinfunction "18_18") (pintype "bidirectional"))
      (node (ref "TP_SPI_DATA_MOSI") (pin "P$1") (pinfunction "P$1_P$1") (pintype "bidirectional"))
    )
    (net (code "82") (name "SPI_DATA_NCS") (class "Default")
      (node (ref "ADC") (pin "29") (pinfunction "~{DRDY}_29") (pintype "output"))
      (node (ref "CON_BACKPLANE") (pin "16") (pinfunction "16_16") (pintype "bidirectional"))
      (node (ref "TP_SPI_DATA_NCS") (pin "P$1") (pinfunction "P$1_P$1") (pintype "bidirectional"))
    )
    (net (code "83") (name "VCM") (class "Default")
      (node (ref "IC5") (pin "9") (pinfunction "VOCM_9") (pintype "passive"))
      (node (ref "IC6") (pin "9") (pinfunction "VOCM_9") (pintype "passive"))
      (node (ref "SJ4") (pin "2") (pinfunction "2_2") (pintype "passive"))
      (node (ref "TP_VCM") (pin "P$1") (pinfunction "P$1_P$1") (pintype "bidirectional"))
    )
    (net (code "84") (name "VCM_ADC") (class "Default")
      (node (ref "C40") (pin "1") (pinfunction "1_1") (pintype "passive"))
      (node (ref "R14") (pin "2") (pinfunction "2_2") (pintype "passive"))
      (node (ref "SJ4") (pin "1") (pinfunction "1_1") (pintype "passive"))
      (node (ref "TP_VCM_ADC") (pin "P$1") (pinfunction "P$1_P$1") (pintype "bidirectional"))
    )
    (net (code "85") (name "VREF_2V5") (class "Default")
      (node (ref "C67") (pin "2") (pinfunction "2_2") (pintype "passive"))
      (node (ref "IC12") (pin "6") (pinfunction "VOUT_6") (pintype "bidirectional"))
      (node (ref "SJ4") (pin "3") (pinfunction "3_3") (pintype "passive"))
      (node (ref "TP_VREF_2V5") (pin "P$1") (pinfunction "P$1_P$1") (pintype "bidirectional"))
    )
    (net (code "86") (name "VREF_5V") (class "Default")
      (node (ref "C31") (pin "2") (pinfunction "2_2") (pintype "passive"))
      (node (ref "IC3") (pin "6") (pinfunction "VOUT_6") (pintype "bidirectional"))
      (node (ref "SJ1") (pin "2") (pinfunction "2_2") (pintype "passive"))
      (node (ref "TP_VREF_5V") (pin "P$1") (pinfunction "P$1_P$1") (pintype "bidirectional"))
    )
    (net (code "87") (name "VREF_5V_BUF") (class "Default")
      (node (ref "R8") (pin "2") (pinfunction "2_2") (pintype "passive"))
      (node (ref "R9") (pin "2") (pinfunction "2_2") (pintype "passive"))
      (node (ref "SJ2") (pin "1") (pinfunction "1_1") (pintype "passive"))
    )
    (net (code "88") (name "unconnected-(ADC-DNC22-Pad22)") (class "Default")
      (node (ref "ADC") (pin "22") (pinfunction "DNC22_22") (pintype "no_connect"))
    )
    (net (code "89") (name "unconnected-(ADC-DNC23-Pad23)") (class "Default")
      (node (ref "ADC") (pin "23") (pinfunction "DNC23_23") (pintype "no_connect"))
    )
    (net (code "90") (name "unconnected-(ADC-DOUT1-Pad26)") (class "Default")
      (node (ref "ADC") (pin "26") (pinfunction "DOUT1_26") (pintype "output"))
    )
    (net (code "91") (name "unconnected-(ADC-DOUT2-Pad25)") (class "Default")
      (node (ref "ADC") (pin "25") (pinfunction "DOUT2_25") (pintype "output"))
    )
    (net (code "92") (name "unconnected-(ADC-DOUT3-Pad24)") (class "Default")
      (node (ref "ADC") (pin "24") (pinfunction "DOUT3_24") (pintype "output"))
    )
    (net (code "93") (name "unconnected-(ADC-FILTER{slash}GPIO4-Pad11)") (class "Default")
      (node (ref "ADC") (pin "11") (pinfunction "FILTER/GPIO4_11") (pintype "bidirectional"))
    )
    (net (code "94") (name "unconnected-(ADC-MODE0{slash}GPIO0-Pad12)") (class "Default")
      (node (ref "ADC") (pin "12") (pinfunction "MODE0/GPIO0_12") (pintype "bidirectional"))
    )
    (net (code "95") (name "unconnected-(ADC-MODE1{slash}GPIO1-Pad13)") (class "Default")
      (node (ref "ADC") (pin "13") (pinfunction "MODE1/GPIO1_13") (pintype "bidirectional"))
    )
    (net (code "96") (name "unconnected-(ADC-MODE2{slash}GPIO2-Pad14)") (class "Default")
      (node (ref "ADC") (pin "14") (pinfunction "MODE2/GPIO2_14") (pintype "bidirectional"))
    )
    (net (code "97") (name "unconnected-(ADC-MODE3{slash}GPIO3-Pad15)") (class "Default")
      (node (ref "ADC") (pin "15") (pinfunction "MODE3/GPIO3_15") (pintype "bidirectional"))
    )
    (net (code "98") (name "unconnected-(IC3-TRIM-Pad5)") (class "Default")
      (node (ref "IC3") (pin "5") (pinfunction "TRIM_5") (pintype "bidirectional"))
    )
    (net (code "99") (name "unconnected-(IC4-~{PD}-Pad5)") (class "Default")
      (node (ref "IC4") (pin "5") (pinfunction "~{PD}_5") (pintype "bidirectional"))
    )
    (net (code "100") (name "unconnected-(IC9-ON1-Pad1)") (class "Default")
      (node (ref "IC9") (pin "1") (pinfunction "ON1_1") (pintype "passive"))
    )
    (net (code "101") (name "unconnected-(IC9-ON2-Pad8)") (class "Default")
      (node (ref "IC9") (pin "8") (pinfunction "ON2_8") (pintype "passive"))
    )
    (net (code "102") (name "unconnected-(IC9-OPT-Pad5)") (class "Default")
      (node (ref "IC9") (pin "5") (pinfunction "OPT_5") (pintype "passive"))
    )
    (net (code "103") (name "unconnected-(IC10-ON1-Pad1)") (class "Default")
      (node (ref "IC10") (pin "1") (pinfunction "ON1_1") (pintype "passive"))
    )
    (net (code "104") (name "unconnected-(IC10-ON2-Pad8)") (class "Default")
      (node (ref "IC10") (pin "8") (pinfunction "ON2_8") (pintype "passive"))
    )
    (net (code "105") (name "unconnected-(IC10-OPT-Pad5)") (class "Default")
      (node (ref "IC10") (pin "5") (pinfunction "OPT_5") (pintype "passive"))
    )
    (net (code "106") (name "unconnected-(IC11-P4-Pad9)") (class "Default")
      (node (ref "IC11") (pin "9") (pinfunction "P4_9") (pintype "bidirectional"))
    )
    (net (code "107") (name "unconnected-(IC11-P5-Pad10)") (class "Default")
      (node (ref "IC11") (pin "10") (pinfunction "P5_10") (pintype "bidirectional"))
    )
    (net (code "108") (name "unconnected-(IC11-P6-Pad11)") (class "Default")
      (node (ref "IC11") (pin "11") (pinfunction "P6_11") (pintype "bidirectional"))
    )
    (net (code "109") (name "unconnected-(IC11-P7-Pad12)") (class "Default")
      (node (ref "IC11") (pin "12") (pinfunction "P7_12") (pintype "bidirectional"))
    )
    (net (code "110") (name "unconnected-(IC12-TRIM-Pad5)") (class "Default")
      (node (ref "IC12") (pin "5") (pinfunction "TRIM_5") (pintype "bidirectional"))
    )
    (net (code "111") (name "unconnected-(RD-OUT5-Pad14)") (class "Default")
      (node (ref "RD") (pin "14") (pinfunction "OUT5_14") (pintype "output"))
    )
    (net (code "112") (name "unconnected-(RD-OUT6-Pad13)") (class "Default")
      (node (ref "RD") (pin "13") (pinfunction "OUT6_13") (pintype "output"))
    )
    (net (code "113") (name "unconnected-(RD-OUT7-Pad11)") (class "Default")
      (node (ref "RD") (pin "11") (pinfunction "OUT7_11") (pintype "output"))
    )
    (net (code "114") (name "unconnected-(RD-OUT8-Pad10)") (class "Default")
      (node (ref "RD") (pin "10") (pinfunction "OUT8_10") (pintype "output"))
    )
    (net (code "115") (name "unconnected-(RELAY1-Pad7)") (class "Default")
      (node (ref "RELAY1") (pin "7") (pinfunction "7_7") (pintype "passive"))
    )
    (net (code "116") (name "unconnected-(RELAY2-Pad7)") (class "Default")
      (node (ref "RELAY2") (pin "7") (pinfunction "7_7") (pintype "passive"))
    )
  )
)
